# tarjeta-v8.net
KiCad netlist of a schematic drawn in EAGLE
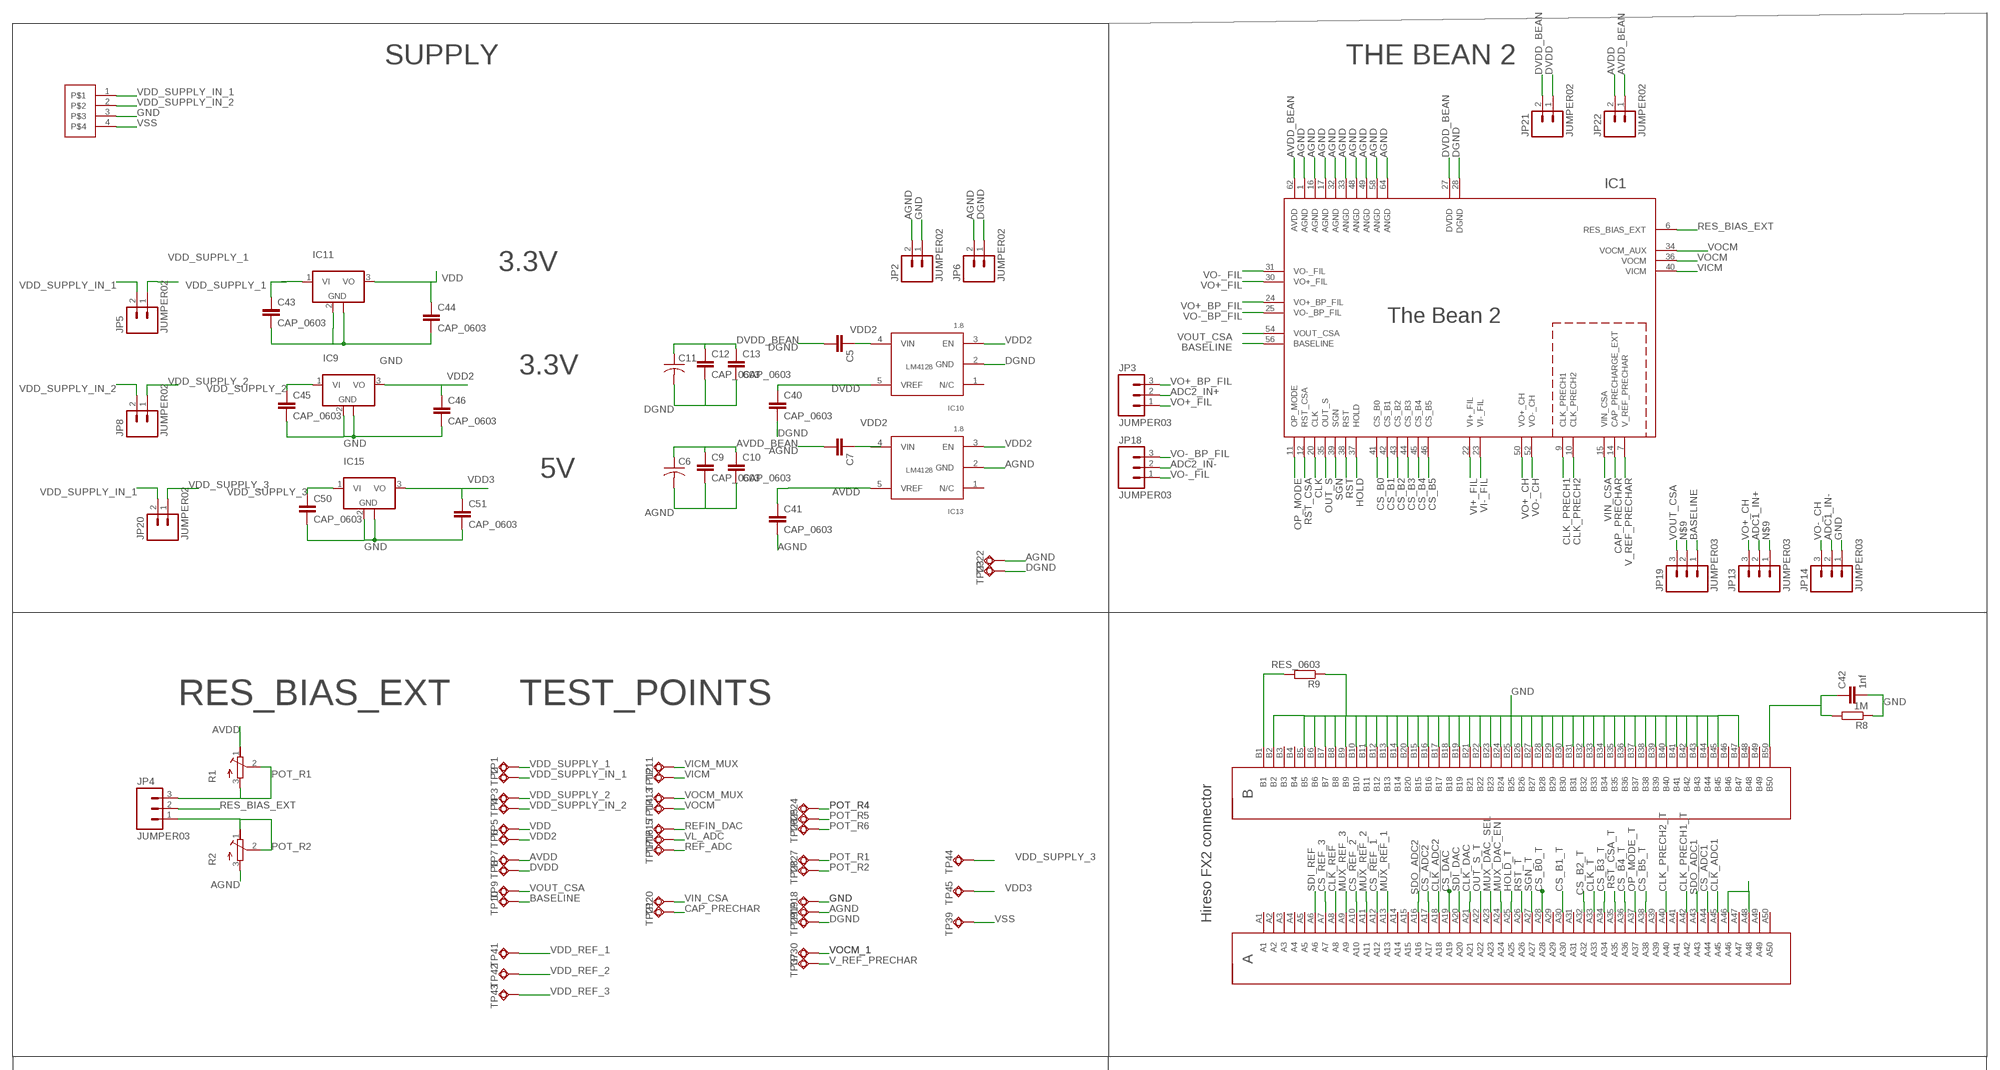
[diagram p0: schematic, sheet 1, part 1 of 3]
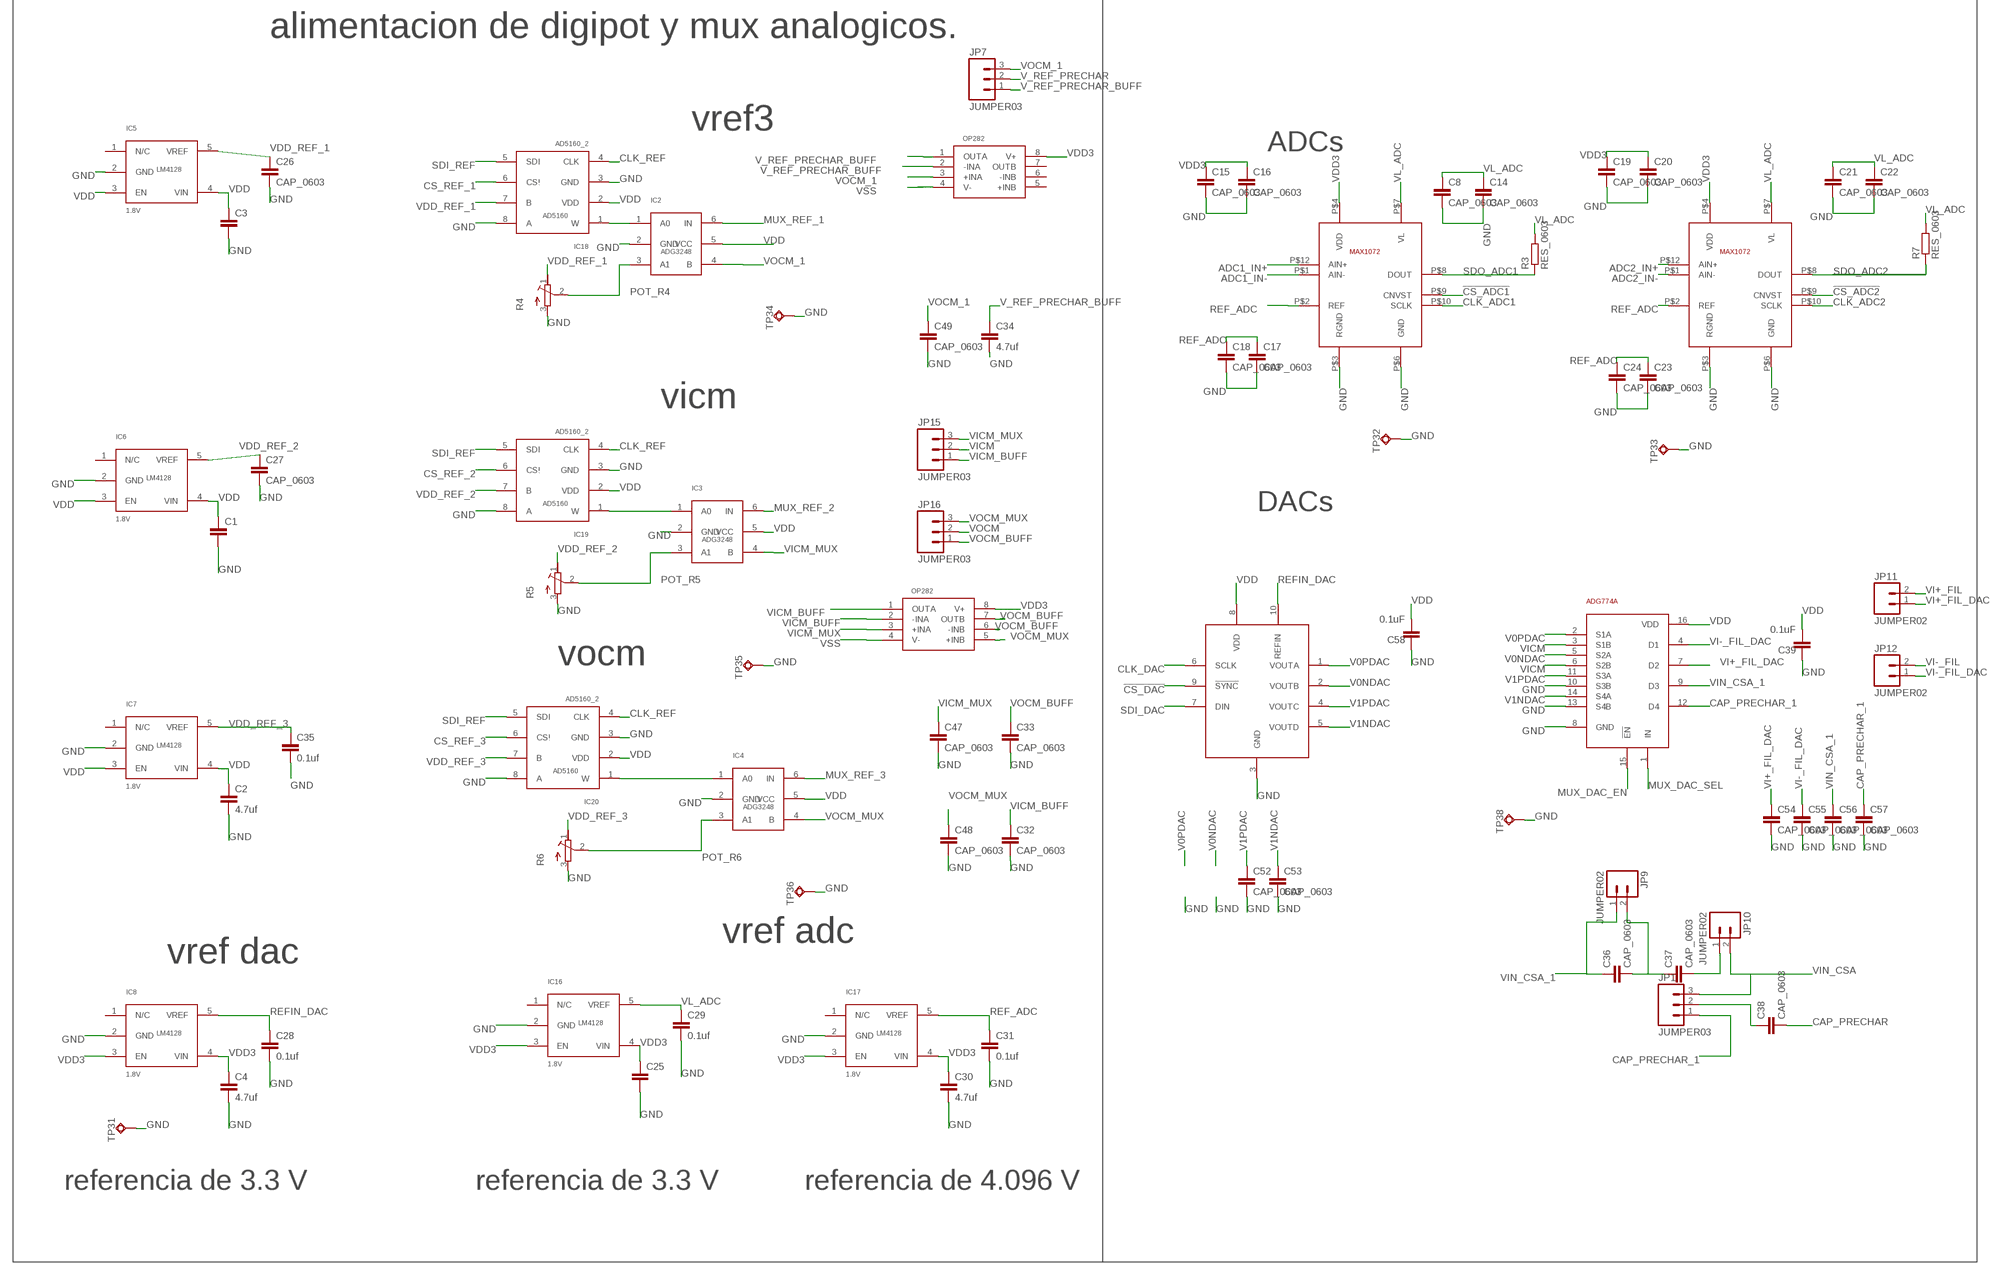
[diagram p1: schematic, sheet 1, part 2 of 3]
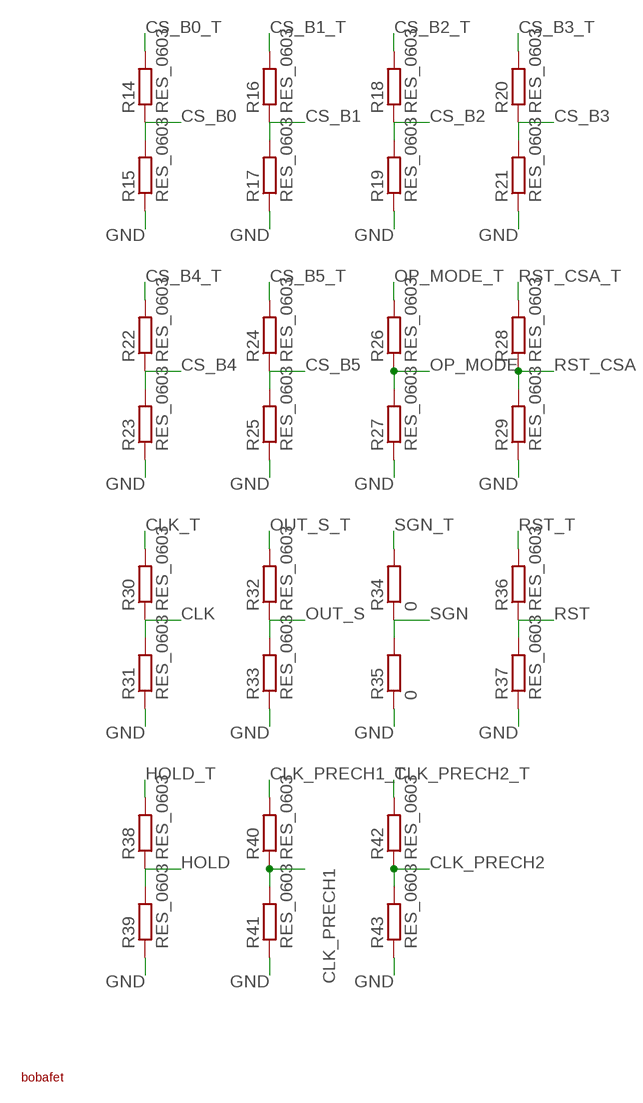
[diagram p2: schematic, sheet 1, part 3 of 3]

(export (version "E")
  (design (tool "Eeschema 10.0.6"))
  (components
    (comp (ref "C1")
      (value "CAP_0402")
      (footprint "eagle-import:C0402")
      (libsource (lib "eagle-import") (part "CAP_0402"))
    )
    (comp (ref "C2")
      (value "4.7uf")
      (footprint "eagle-import:C0402")
      (libsource (lib "eagle-import") (part "CAP_0402"))
    )
    (comp (ref "C3")
      (value "CAP_0402")
      (footprint "eagle-import:C0402")
      (libsource (lib "eagle-import") (part "CAP_0402"))
    )
    (comp (ref "C4")
      (value "4.7uf")
      (footprint "eagle-import:C0402")
      (libsource (lib "eagle-import") (part "CAP_0402"))
    )
    (comp (ref "C5")
      (value "CAP_0402")
      (footprint "eagle-import:C0402")
      (libsource (lib "eagle-import") (part "CAP_0402"))
    )
    (comp (ref "C6")
      (value "CAP_0805")
      (footprint "eagle-import:C0805")
      (libsource (lib "eagle-import") (part "CAP_0805"))
    )
    (comp (ref "C7")
      (value "CAP_0402")
      (footprint "eagle-import:C0402")
      (libsource (lib "eagle-import") (part "CAP_0402"))
    )
    (comp (ref "C8")
      (value "CAP_0603")
      (footprint "eagle-import:C0603")
      (libsource (lib "eagle-import") (part "CAP_0603"))
    )
    (comp (ref "C9")
      (value "CAP_0603")
      (footprint "eagle-import:C0603")
      (libsource (lib "eagle-import") (part "CAP_0603"))
    )
    (comp (ref "C10")
      (value "CAP_0603")
      (footprint "eagle-import:C0603")
      (libsource (lib "eagle-import") (part "CAP_0603"))
    )
    (comp (ref "C11")
      (value "CAP_0805")
      (footprint "eagle-import:C0805")
      (libsource (lib "eagle-import") (part "CAP_0805"))
    )
    (comp (ref "C12")
      (value "CAP_0603")
      (footprint "eagle-import:C0603")
      (libsource (lib "eagle-import") (part "CAP_0603"))
    )
    (comp (ref "C13")
      (value "CAP_0603")
      (footprint "eagle-import:C0603")
      (libsource (lib "eagle-import") (part "CAP_0603"))
    )
    (comp (ref "C14")
      (value "CAP_0603")
      (footprint "eagle-import:C0603")
      (libsource (lib "eagle-import") (part "CAP_0603"))
    )
    (comp (ref "C15")
      (value "CAP_0603")
      (footprint "eagle-import:C0603")
      (libsource (lib "eagle-import") (part "CAP_0603"))
    )
    (comp (ref "C16")
      (value "CAP_0603")
      (footprint "eagle-import:C0603")
      (libsource (lib "eagle-import") (part "CAP_0603"))
    )
    (comp (ref "C17")
      (value "CAP_0603")
      (footprint "eagle-import:C0603")
      (libsource (lib "eagle-import") (part "CAP_0603"))
    )
    (comp (ref "C18")
      (value "CAP_0603")
      (footprint "eagle-import:C0603")
      (libsource (lib "eagle-import") (part "CAP_0603"))
    )
    (comp (ref "C19")
      (value "CAP_0603")
      (footprint "eagle-import:C0603")
      (libsource (lib "eagle-import") (part "CAP_0603"))
    )
    (comp (ref "C20")
      (value "CAP_0603")
      (footprint "eagle-import:C0603")
      (libsource (lib "eagle-import") (part "CAP_0603"))
    )
    (comp (ref "C21")
      (value "CAP_0603")
      (footprint "eagle-import:C0603")
      (libsource (lib "eagle-import") (part "CAP_0603"))
    )
    (comp (ref "C22")
      (value "CAP_0603")
      (footprint "eagle-import:C0603")
      (libsource (lib "eagle-import") (part "CAP_0603"))
    )
    (comp (ref "C23")
      (value "CAP_0603")
      (footprint "eagle-import:C0603")
      (libsource (lib "eagle-import") (part "CAP_0603"))
    )
    (comp (ref "C24")
      (value "CAP_0603")
      (footprint "eagle-import:C0603")
      (libsource (lib "eagle-import") (part "CAP_0603"))
    )
    (comp (ref "C25")
      (value "CAP_0402")
      (footprint "eagle-import:C0402")
      (libsource (lib "eagle-import") (part "CAP_0402"))
    )
    (comp (ref "C26")
      (value "CAP_0603")
      (footprint "eagle-import:C0603")
      (libsource (lib "eagle-import") (part "CAP_0603"))
    )
    (comp (ref "C27")
      (value "CAP_0603")
      (footprint "eagle-import:C0603")
      (libsource (lib "eagle-import") (part "CAP_0603"))
    )
    (comp (ref "C28")
      (value "0.1uf")
      (footprint "eagle-import:C0603")
      (libsource (lib "eagle-import") (part "CAP_0603"))
    )
    (comp (ref "C29")
      (value "0.1uf")
      (footprint "eagle-import:C0603")
      (libsource (lib "eagle-import") (part "CAP_0603"))
    )
    (comp (ref "C30")
      (value "4.7uf")
      (footprint "eagle-import:C0402")
      (libsource (lib "eagle-import") (part "CAP_0402"))
    )
    (comp (ref "C31")
      (value "0.1uf")
      (footprint "eagle-import:C0603")
      (libsource (lib "eagle-import") (part "CAP_0603"))
    )
    (comp (ref "C32")
      (value "CAP_0603")
      (footprint "eagle-import:C0603")
      (libsource (lib "eagle-import") (part "CAP_0603"))
    )
    (comp (ref "C33")
      (value "CAP_0603")
      (footprint "eagle-import:C0603")
      (libsource (lib "eagle-import") (part "CAP_0603"))
    )
    (comp (ref "C34")
      (value "4.7uf")
      (footprint "eagle-import:C0603")
      (libsource (lib "eagle-import") (part "CAP_0603"))
    )
    (comp (ref "C35")
      (value "0.1uf")
      (footprint "eagle-import:C0603")
      (libsource (lib "eagle-import") (part "CAP_0603"))
    )
    (comp (ref "C36")
      (value "CAP_0603")
      (footprint "eagle-import:C0603")
      (libsource (lib "eagle-import") (part "CAP_0603"))
    )
    (comp (ref "C37")
      (value "CAP_0603")
      (footprint "eagle-import:C0603")
      (libsource (lib "eagle-import") (part "CAP_0603"))
    )
    (comp (ref "C38")
      (value "CAP_0603")
      (footprint "eagle-import:C0603")
      (libsource (lib "eagle-import") (part "CAP_0603"))
    )
    (comp (ref "C39")
      (value "0.1uF")
      (footprint "eagle-import:C0603")
      (libsource (lib "eagle-import") (part "CAP_0603"))
    )
    (comp (ref "C40")
      (value "CAP_0603")
      (footprint "eagle-import:C0603")
      (libsource (lib "eagle-import") (part "CAP_0603"))
    )
    (comp (ref "C41")
      (value "CAP_0603")
      (footprint "eagle-import:C0603")
      (libsource (lib "eagle-import") (part "CAP_0603"))
    )
    (comp (ref "C42")
      (value "1nf")
      (footprint "eagle-import:C0603")
      (libsource (lib "eagle-import") (part "CAP_0603"))
    )
    (comp (ref "C43")
      (value "CAP_0603")
      (footprint "eagle-import:C0603")
      (libsource (lib "eagle-import") (part "CAP_0603"))
    )
    (comp (ref "C44")
      (value "CAP_0603")
      (footprint "eagle-import:C0603")
      (libsource (lib "eagle-import") (part "CAP_0603"))
    )
    (comp (ref "C45")
      (value "CAP_0603")
      (footprint "eagle-import:C0603")
      (libsource (lib "eagle-import") (part "CAP_0603"))
    )
    (comp (ref "C46")
      (value "CAP_0603")
      (footprint "eagle-import:C0603")
      (libsource (lib "eagle-import") (part "CAP_0603"))
    )
    (comp (ref "C47")
      (value "CAP_0603")
      (footprint "eagle-import:C0603")
      (libsource (lib "eagle-import") (part "CAP_0603"))
    )
    (comp (ref "C48")
      (value "CAP_0603")
      (footprint "eagle-import:C0603")
      (libsource (lib "eagle-import") (part "CAP_0603"))
    )
    (comp (ref "C49")
      (value "CAP_0603")
      (footprint "eagle-import:C0603")
      (libsource (lib "eagle-import") (part "CAP_0603"))
    )
    (comp (ref "C50")
      (value "CAP_0603")
      (footprint "eagle-import:C0603")
      (libsource (lib "eagle-import") (part "CAP_0603"))
    )
    (comp (ref "C51")
      (value "CAP_0603")
      (footprint "eagle-import:C0603")
      (libsource (lib "eagle-import") (part "CAP_0603"))
    )
    (comp (ref "C52")
      (value "CAP_0603")
      (footprint "eagle-import:C0603")
      (libsource (lib "eagle-import") (part "CAP_0603"))
    )
    (comp (ref "C53")
      (value "CAP_0603")
      (footprint "eagle-import:C0603")
      (libsource (lib "eagle-import") (part "CAP_0603"))
    )
    (comp (ref "C54")
      (value "CAP_0603")
      (footprint "eagle-import:C0603")
      (libsource (lib "eagle-import") (part "CAP_0603"))
    )
    (comp (ref "C55")
      (value "CAP_0603")
      (footprint "eagle-import:C0603")
      (libsource (lib "eagle-import") (part "CAP_0603"))
    )
    (comp (ref "C56")
      (value "CAP_0603")
      (footprint "eagle-import:C0603")
      (libsource (lib "eagle-import") (part "CAP_0603"))
    )
    (comp (ref "C57")
      (value "CAP_0603")
      (footprint "eagle-import:C0603")
      (libsource (lib "eagle-import") (part "CAP_0603"))
    )
    (comp (ref "C58")
      (value "0.1uF")
      (footprint "eagle-import:C0603")
      (libsource (lib "eagle-import") (part "CAP_0603"))
    )
    (comp (ref "IC1")
      (value "THE_BEAN_2")
      (footprint "eagle-import:QFN64")
      (libsource (lib "eagle-import") (part "THE_BEAN_2"))
    )
    (comp (ref "IC2")
      (value "ADG3248")
      (footprint "eagle-import:SC70")
      (libsource (lib "eagle-import") (part "ADG3248"))
    )
    (comp (ref "IC3")
      (value "ADG3248")
      (footprint "eagle-import:SC70")
      (libsource (lib "eagle-import") (part "ADG3248"))
    )
    (comp (ref "IC4")
      (value "ADG3248")
      (footprint "eagle-import:SC70")
      (libsource (lib "eagle-import") (part "ADG3248"))
    )
    (comp (ref "IC5")
      (value "1.8V")
      (footprint "eagle-import:SOT23-5L_2")
      (libsource (lib "eagle-import") (part "LM4128_2"))
    )
    (comp (ref "IC6")
      (value "1.8V")
      (footprint "eagle-import:SOT23-5L_2")
      (libsource (lib "eagle-import") (part "LM4128_2"))
    )
    (comp (ref "IC7")
      (value "1.8V")
      (footprint "eagle-import:SOT23-5L_2")
      (libsource (lib "eagle-import") (part "LM4128_2"))
    )
    (comp (ref "IC8")
      (value "1.8V")
      (footprint "eagle-import:SOT23-5L_2")
      (libsource (lib "eagle-import") (part "LM4128_2"))
    )
    (comp (ref "IC9")
      (value "UA78M")
      (footprint "eagle-import:SOT223")
      (libsource (lib "eagle-import") (part "UA78M"))
    )
    (comp (ref "IC10")
      (value "1.8")
      (footprint "eagle-import:SOT23-5L_2")
      (libsource (lib "eagle-import") (part "LM4128_2"))
    )
    (comp (ref "IC11")
      (value "UA78M")
      (footprint "eagle-import:SOT223")
      (libsource (lib "eagle-import") (part "UA78M"))
    )
    (comp (ref "IC12")
      (value "OP282")
      (footprint "eagle-import:SOIC8")
      (libsource (lib "eagle-import") (part "OP282"))
    )
    (comp (ref "IC13")
      (value "1.8")
      (footprint "eagle-import:SOT23-5L_2")
      (libsource (lib "eagle-import") (part "LM4128_2"))
    )
    (comp (ref "IC14")
      (value "OP282")
      (footprint "eagle-import:SOIC8")
      (libsource (lib "eagle-import") (part "OP282"))
    )
    (comp (ref "IC15")
      (value "UA78M")
      (footprint "eagle-import:SOT223")
      (libsource (lib "eagle-import") (part "UA78M"))
    )
    (comp (ref "IC16")
      (value "1.8V")
      (footprint "eagle-import:SOT23-5L_2")
      (libsource (lib "eagle-import") (part "LM4128_2"))
    )
    (comp (ref "IC17")
      (value "1.8V")
      (footprint "eagle-import:SOT23-5L_2")
      (libsource (lib "eagle-import") (part "LM4128_2"))
    )
    (comp (ref "IC18")
      (value "AD5160_2")
      (footprint "eagle-import:SOT23-8_2")
      (libsource (lib "eagle-import") (part "AD5160_2"))
    )
    (comp (ref "IC19")
      (value "AD5160_2")
      (footprint "eagle-import:SOT23-8_2")
      (libsource (lib "eagle-import") (part "AD5160_2"))
    )
    (comp (ref "IC20")
      (value "AD5160_2")
      (footprint "eagle-import:SOT23-8_2")
      (libsource (lib "eagle-import") (part "AD5160_2"))
    )
    (comp (ref "IC21")
      (value "ADG774A")
      (footprint "eagle-import:QSOP16")
      (libsource (lib "eagle-import") (part "ADG774A"))
    )
    (comp (ref "IC22")
      (value "MAX1072")
      (footprint "eagle-import:TQFN12")
      (libsource (lib "eagle-import") (part "MAX1072"))
    )
    (comp (ref "IC23")
      (value "DAC7554")
      (footprint "eagle-import:MSOP10")
      (libsource (lib "eagle-import") (part "DAC7554"))
    )
    (comp (ref "IC24")
      (value "MAX1072")
      (footprint "eagle-import:TQFN12")
      (libsource (lib "eagle-import") (part "MAX1072"))
    )
    (comp (ref "J1")
      (value "HIRESO_FX_CONNECTOR")
      (footprint "eagle-import:FX2-100S-1.27")
      (libsource (lib "eagle-import") (part "HIRESO_FX_CONNECTOR"))
    )
    (comp (ref "JP1")
      (value "JUMPER03")
      (footprint "eagle-import:1X03")
      (libsource (lib "eagle-import") (part "JUMPER03"))
    )
    (comp (ref "JP2")
      (value "JUMPER02")
      (footprint "eagle-import:1X02")
      (libsource (lib "eagle-import") (part "JUMPER02"))
    )
    (comp (ref "JP3")
      (value "JUMPER03")
      (footprint "eagle-import:1X03")
      (libsource (lib "eagle-import") (part "JUMPER03"))
    )
    (comp (ref "JP4")
      (value "JUMPER03")
      (footprint "eagle-import:1X03")
      (libsource (lib "eagle-import") (part "JUMPER03"))
    )
    (comp (ref "JP5")
      (value "JUMPER02")
      (footprint "eagle-import:1X02")
      (libsource (lib "eagle-import") (part "JUMPER02"))
    )
    (comp (ref "JP6")
      (value "JUMPER02")
      (footprint "eagle-import:1X02")
      (libsource (lib "eagle-import") (part "JUMPER02"))
    )
    (comp (ref "JP7")
      (value "JUMPER03")
      (footprint "eagle-import:1X03")
      (libsource (lib "eagle-import") (part "JUMPER03"))
    )
    (comp (ref "JP8")
      (value "JUMPER02")
      (footprint "eagle-import:1X02")
      (libsource (lib "eagle-import") (part "JUMPER02"))
    )
    (comp (ref "JP9")
      (value "JUMPER02")
      (footprint "eagle-import:1X02")
      (libsource (lib "eagle-import") (part "JUMPER02"))
    )
    (comp (ref "JP10")
      (value "JUMPER02")
      (footprint "eagle-import:1X02")
      (libsource (lib "eagle-import") (part "JUMPER02"))
    )
    (comp (ref "JP11")
      (value "JUMPER02")
      (footprint "eagle-import:1X02")
      (libsource (lib "eagle-import") (part "JUMPER02"))
    )
    (comp (ref "JP12")
      (value "JUMPER02")
      (footprint "eagle-import:1X02")
      (libsource (lib "eagle-import") (part "JUMPER02"))
    )
    (comp (ref "JP13")
      (value "JUMPER03")
      (footprint "eagle-import:1X03")
      (libsource (lib "eagle-import") (part "JUMPER03"))
    )
    (comp (ref "JP14")
      (value "JUMPER03")
      (footprint "eagle-import:1X03")
      (libsource (lib "eagle-import") (part "JUMPER03"))
    )
    (comp (ref "JP15")
      (value "JUMPER03")
      (footprint "eagle-import:1X03")
      (libsource (lib "eagle-import") (part "JUMPER03"))
    )
    (comp (ref "JP16")
      (value "JUMPER03")
      (footprint "eagle-import:1X03")
      (libsource (lib "eagle-import") (part "JUMPER03"))
    )
    (comp (ref "JP17")
      (value "JUMPER04")
      (footprint "eagle-import:1X04")
      (libsource (lib "eagle-import") (part "JUMPER04"))
    )
    (comp (ref "JP18")
      (value "JUMPER03")
      (footprint "eagle-import:1X03")
      (libsource (lib "eagle-import") (part "JUMPER03"))
    )
    (comp (ref "JP19")
      (value "JUMPER03")
      (footprint "eagle-import:1X03")
      (libsource (lib "eagle-import") (part "JUMPER03"))
    )
    (comp (ref "JP20")
      (value "JUMPER02")
      (footprint "eagle-import:1X02")
      (libsource (lib "eagle-import") (part "JUMPER02"))
    )
    (comp (ref "JP21")
      (value "JUMPER02")
      (footprint "eagle-import:1X02")
      (libsource (lib "eagle-import") (part "JUMPER02"))
    )
    (comp (ref "JP22")
      (value "JUMPER02")
      (footprint "eagle-import:1X02")
      (libsource (lib "eagle-import") (part "JUMPER02"))
    )
    (comp (ref "R1")
      (value "TRIMMER_ST5")
      (footprint "eagle-import:ST-5EW")
      (libsource (lib "eagle-import") (part "TRIMMER_ST5"))
    )
    (comp (ref "R2")
      (value "TRIMMER_ST5")
      (footprint "eagle-import:ST-5EW")
      (libsource (lib "eagle-import") (part "TRIMMER_ST5"))
    )
    (comp (ref "R3")
      (value "RES_0603")
      (footprint "eagle-import:R0603")
      (libsource (lib "eagle-import") (part "RES_0603"))
    )
    (comp (ref "R4")
      (value "TRIMMER_ST5")
      (footprint "eagle-import:ST-5EW")
      (libsource (lib "eagle-import") (part "TRIMMER_ST5"))
    )
    (comp (ref "R5")
      (value "TRIMMER_ST5")
      (footprint "eagle-import:ST-5EW")
      (libsource (lib "eagle-import") (part "TRIMMER_ST5"))
    )
    (comp (ref "R6")
      (value "TRIMMER_ST5")
      (footprint "eagle-import:ST-5EW")
      (libsource (lib "eagle-import") (part "TRIMMER_ST5"))
    )
    (comp (ref "R7")
      (value "RES_0603")
      (footprint "eagle-import:R0603")
      (libsource (lib "eagle-import") (part "RES_0603"))
    )
    (comp (ref "R8")
      (value "1M")
      (footprint "eagle-import:R0603")
      (libsource (lib "eagle-import") (part "RES_0603"))
    )
    (comp (ref "R9")
      (value "RES_0603")
      (footprint "eagle-import:R0603")
      (libsource (lib "eagle-import") (part "RES_0603"))
    )
    (comp (ref "R14")
      (value "RES_0603")
      (footprint "eagle-import:R0603")
      (libsource (lib "eagle-import") (part "RES_0603"))
    )
    (comp (ref "R15")
      (value "RES_0603")
      (footprint "eagle-import:R0603")
      (libsource (lib "eagle-import") (part "RES_0603"))
    )
    (comp (ref "R16")
      (value "RES_0603")
      (footprint "eagle-import:R0603")
      (libsource (lib "eagle-import") (part "RES_0603"))
    )
    (comp (ref "R17")
      (value "RES_0603")
      (footprint "eagle-import:R0603")
      (libsource (lib "eagle-import") (part "RES_0603"))
    )
    (comp (ref "R18")
      (value "RES_0603")
      (footprint "eagle-import:R0603")
      (libsource (lib "eagle-import") (part "RES_0603"))
    )
    (comp (ref "R19")
      (value "RES_0603")
      (footprint "eagle-import:R0603")
      (libsource (lib "eagle-import") (part "RES_0603"))
    )
    (comp (ref "R20")
      (value "RES_0603")
      (footprint "eagle-import:R0603")
      (libsource (lib "eagle-import") (part "RES_0603"))
    )
    (comp (ref "R21")
      (value "RES_0603")
      (footprint "eagle-import:R0603")
      (libsource (lib "eagle-import") (part "RES_0603"))
    )
    (comp (ref "R22")
      (value "RES_0603")
      (footprint "eagle-import:R0603")
      (libsource (lib "eagle-import") (part "RES_0603"))
    )
    (comp (ref "R23")
      (value "RES_0603")
      (footprint "eagle-import:R0603")
      (libsource (lib "eagle-import") (part "RES_0603"))
    )
    (comp (ref "R24")
      (value "RES_0603")
      (footprint "eagle-import:R0603")
      (libsource (lib "eagle-import") (part "RES_0603"))
    )
    (comp (ref "R25")
      (value "RES_0603")
      (footprint "eagle-import:R0603")
      (libsource (lib "eagle-import") (part "RES_0603"))
    )
    (comp (ref "R26")
      (value "RES_0603")
      (footprint "eagle-import:R0603")
      (libsource (lib "eagle-import") (part "RES_0603"))
    )
    (comp (ref "R27")
      (value "RES_0603")
      (footprint "eagle-import:R0603")
      (libsource (lib "eagle-import") (part "RES_0603"))
    )
    (comp (ref "R28")
      (value "RES_0603")
      (footprint "eagle-import:R0603")
      (libsource (lib "eagle-import") (part "RES_0603"))
    )
    (comp (ref "R29")
      (value "RES_0603")
      (footprint "eagle-import:R0603")
      (libsource (lib "eagle-import") (part "RES_0603"))
    )
    (comp (ref "R30")
      (value "RES_0603")
      (footprint "eagle-import:R0603")
      (libsource (lib "eagle-import") (part "RES_0603"))
    )
    (comp (ref "R31")
      (value "RES_0603")
      (footprint "eagle-import:R0603")
      (libsource (lib "eagle-import") (part "RES_0603"))
    )
    (comp (ref "R32")
      (value "RES_0603")
      (footprint "eagle-import:R0603")
      (libsource (lib "eagle-import") (part "RES_0603"))
    )
    (comp (ref "R33")
      (value "RES_0603")
      (footprint "eagle-import:R0603")
      (libsource (lib "eagle-import") (part "RES_0603"))
    )
    (comp (ref "R34")
      (value "0")
      (footprint "eagle-import:R0603")
      (libsource (lib "eagle-import") (part "RES_0603"))
    )
    (comp (ref "R35")
      (value "0")
      (footprint "eagle-import:R0603")
      (libsource (lib "eagle-import") (part "RES_0603"))
    )
    (comp (ref "R36")
      (value "RES_0603")
      (footprint "eagle-import:R0603")
      (libsource (lib "eagle-import") (part "RES_0603"))
    )
    (comp (ref "R37")
      (value "RES_0603")
      (footprint "eagle-import:R0603")
      (libsource (lib "eagle-import") (part "RES_0603"))
    )
    (comp (ref "R38")
      (value "RES_0603")
      (footprint "eagle-import:R0603")
      (libsource (lib "eagle-import") (part "RES_0603"))
    )
    (comp (ref "R39")
      (value "RES_0603")
      (footprint "eagle-import:R0603")
      (libsource (lib "eagle-import") (part "RES_0603"))
    )
    (comp (ref "R40")
      (value "RES_0603")
      (footprint "eagle-import:R0603")
      (libsource (lib "eagle-import") (part "RES_0603"))
    )
    (comp (ref "R41")
      (value "RES_0603")
      (footprint "eagle-import:R0603")
      (libsource (lib "eagle-import") (part "RES_0603"))
    )
    (comp (ref "R42")
      (value "RES_0603")
      (footprint "eagle-import:R0603")
      (libsource (lib "eagle-import") (part "RES_0603"))
    )
    (comp (ref "R43")
      (value "RES_0603")
      (footprint "eagle-import:R0603")
      (libsource (lib "eagle-import") (part "RES_0603"))
    )
    (comp (ref "TP1")
      (value "TEST_POINT")
      (footprint "eagle-import:TP")
      (libsource (lib "eagle-import") (part "TEST_POINT"))
    )
    (comp (ref "TP2")
      (value "TEST_POINT")
      (footprint "eagle-import:TP")
      (libsource (lib "eagle-import") (part "TEST_POINT"))
    )
    (comp (ref "TP3")
      (value "TEST_POINT")
      (footprint "eagle-import:TP")
      (libsource (lib "eagle-import") (part "TEST_POINT"))
    )
    (comp (ref "TP4")
      (value "TEST_POINT")
      (footprint "eagle-import:TP")
      (libsource (lib "eagle-import") (part "TEST_POINT"))
    )
    (comp (ref "TP5")
      (value "TEST_POINT")
      (footprint "eagle-import:TP")
      (libsource (lib "eagle-import") (part "TEST_POINT"))
    )
    (comp (ref "TP6")
      (value "TEST_POINT")
      (footprint "eagle-import:TP")
      (libsource (lib "eagle-import") (part "TEST_POINT"))
    )
    (comp (ref "TP7")
      (value "TEST_POINT")
      (footprint "eagle-import:TP")
      (libsource (lib "eagle-import") (part "TEST_POINT"))
    )
    (comp (ref "TP8")
      (value "TEST_POINT")
      (footprint "eagle-import:TP")
      (libsource (lib "eagle-import") (part "TEST_POINT"))
    )
    (comp (ref "TP9")
      (value "TEST_POINT")
      (footprint "eagle-import:TP")
      (libsource (lib "eagle-import") (part "TEST_POINT"))
    )
    (comp (ref "TP10")
      (value "TEST_POINT")
      (footprint "eagle-import:TP")
      (libsource (lib "eagle-import") (part "TEST_POINT"))
    )
    (comp (ref "TP11")
      (value "TEST_POINT")
      (footprint "eagle-import:TP")
      (libsource (lib "eagle-import") (part "TEST_POINT"))
    )
    (comp (ref "TP12")
      (value "TEST_POINT")
      (footprint "eagle-import:TP")
      (libsource (lib "eagle-import") (part "TEST_POINT"))
    )
    (comp (ref "TP13")
      (value "TEST_POINT")
      (footprint "eagle-import:TP")
      (libsource (lib "eagle-import") (part "TEST_POINT"))
    )
    (comp (ref "TP14")
      (value "TEST_POINT")
      (footprint "eagle-import:TP")
      (libsource (lib "eagle-import") (part "TEST_POINT"))
    )
    (comp (ref "TP15")
      (value "TEST_POINT")
      (footprint "eagle-import:TP")
      (libsource (lib "eagle-import") (part "TEST_POINT"))
    )
    (comp (ref "TP16")
      (value "TEST_POINT")
      (footprint "eagle-import:TP")
      (libsource (lib "eagle-import") (part "TEST_POINT"))
    )
    (comp (ref "TP17")
      (value "TEST_POINT")
      (footprint "eagle-import:TP")
      (libsource (lib "eagle-import") (part "TEST_POINT"))
    )
    (comp (ref "TP18")
      (value "TEST_POINT")
      (footprint "eagle-import:TP")
      (libsource (lib "eagle-import") (part "TEST_POINT"))
    )
    (comp (ref "TP19")
      (value "TEST_POINT")
      (footprint "eagle-import:TP")
      (libsource (lib "eagle-import") (part "TEST_POINT"))
    )
    (comp (ref "TP20")
      (value "TEST_POINT")
      (footprint "eagle-import:TP")
      (libsource (lib "eagle-import") (part "TEST_POINT"))
    )
    (comp (ref "TP21")
      (value "TEST_POINT")
      (footprint "eagle-import:TP")
      (libsource (lib "eagle-import") (part "TEST_POINT"))
    )
    (comp (ref "TP22")
      (value "TEST_POINT")
      (footprint "eagle-import:TP")
      (libsource (lib "eagle-import") (part "TEST_POINT"))
    )
    (comp (ref "TP23")
      (value "TEST_POINT")
      (footprint "eagle-import:TP")
      (libsource (lib "eagle-import") (part "TEST_POINT"))
    )
    (comp (ref "TP24")
      (value "TEST_POINT")
      (footprint "eagle-import:TP")
      (libsource (lib "eagle-import") (part "TEST_POINT"))
    )
    (comp (ref "TP25")
      (value "TEST_POINT")
      (footprint "eagle-import:TP")
      (libsource (lib "eagle-import") (part "TEST_POINT"))
    )
    (comp (ref "TP26")
      (value "TEST_POINT")
      (footprint "eagle-import:TP")
      (libsource (lib "eagle-import") (part "TEST_POINT"))
    )
    (comp (ref "TP27")
      (value "TEST_POINT")
      (footprint "eagle-import:TP")
      (libsource (lib "eagle-import") (part "TEST_POINT"))
    )
    (comp (ref "TP28")
      (value "TEST_POINT")
      (footprint "eagle-import:TP")
      (libsource (lib "eagle-import") (part "TEST_POINT"))
    )
    (comp (ref "TP29")
      (value "TEST_POINT")
      (footprint "eagle-import:TP")
      (libsource (lib "eagle-import") (part "TEST_POINT"))
    )
    (comp (ref "TP30")
      (value "TEST_POINT")
      (footprint "eagle-import:TP")
      (libsource (lib "eagle-import") (part "TEST_POINT"))
    )
    (comp (ref "TP31")
      (value "TEST_POINT")
      (footprint "eagle-import:TP")
      (libsource (lib "eagle-import") (part "TEST_POINT"))
    )
    (comp (ref "TP32")
      (value "TEST_POINT")
      (footprint "eagle-import:TP")
      (libsource (lib "eagle-import") (part "TEST_POINT"))
    )
    (comp (ref "TP33")
      (value "TEST_POINT")
      (footprint "eagle-import:TP")
      (libsource (lib "eagle-import") (part "TEST_POINT"))
    )
    (comp (ref "TP34")
      (value "TEST_POINT")
      (footprint "eagle-import:TP")
      (libsource (lib "eagle-import") (part "TEST_POINT"))
    )
    (comp (ref "TP35")
      (value "TEST_POINT")
      (footprint "eagle-import:TP")
      (libsource (lib "eagle-import") (part "TEST_POINT"))
    )
    (comp (ref "TP36")
      (value "TEST_POINT")
      (footprint "eagle-import:TP")
      (libsource (lib "eagle-import") (part "TEST_POINT"))
    )
    (comp (ref "TP37")
      (value "TEST_POINT")
      (footprint "eagle-import:TP")
      (libsource (lib "eagle-import") (part "TEST_POINT"))
    )
    (comp (ref "TP38")
      (value "TEST_POINT")
      (footprint "eagle-import:TP")
      (libsource (lib "eagle-import") (part "TEST_POINT"))
    )
    (comp (ref "TP39")
      (value "TEST_POINT")
      (footprint "eagle-import:TP")
      (libsource (lib "eagle-import") (part "TEST_POINT"))
    )
    (comp (ref "TP41")
      (value "TEST_POINT")
      (footprint "eagle-import:TP")
      (libsource (lib "eagle-import") (part "TEST_POINT"))
    )
    (comp (ref "TP42")
      (value "TEST_POINT")
      (footprint "eagle-import:TP")
      (libsource (lib "eagle-import") (part "TEST_POINT"))
    )
    (comp (ref "TP43")
      (value "TEST_POINT")
      (footprint "eagle-import:TP")
      (libsource (lib "eagle-import") (part "TEST_POINT"))
    )
    (comp (ref "TP44")
      (value "TEST_POINT")
      (footprint "eagle-import:TP")
      (libsource (lib "eagle-import") (part "TEST_POINT"))
    )
    (comp (ref "TP45")
      (value "TEST_POINT")
      (footprint "eagle-import:TP")
      (libsource (lib "eagle-import") (part "TEST_POINT"))
    )
    (comp (ref "U$1")
      (value "LOGO")
      (footprint "eagle-import:LOGO")
      (libsource (lib "eagle-import") (part "LOGO"))
    )
  )
  (nets
    (net (code "1") (name "/ADC1_IN+") (class "Default")
      (node (ref "IC22") (pin "P$12") (pinfunction "AIN+_P$12") (pintype "bidirectional"))
      (node (ref "JP13") (pin "2") (pinfunction "2_2") (pintype "passive"))
    )
    (net (code "2") (name "/ADC1_IN-") (class "Default")
      (node (ref "IC22") (pin "P$1") (pinfunction "AIN-_P$1") (pintype "bidirectional"))
      (node (ref "JP14") (pin "2") (pinfunction "2_2") (pintype "passive"))
    )
    (net (code "3") (name "/ADC2_IN+") (class "Default")
      (node (ref "IC24") (pin "P$12") (pinfunction "AIN+_P$12") (pintype "bidirectional"))
      (node (ref "JP3") (pin "2") (pinfunction "2_2") (pintype "passive"))
    )
    (net (code "4") (name "/ADC2_IN-") (class "Default")
      (node (ref "IC24") (pin "P$1") (pinfunction "AIN-_P$1") (pintype "bidirectional"))
      (node (ref "JP18") (pin "2") (pinfunction "2_2") (pintype "passive"))
    )
    (net (code "5") (name "/AGND") (class "Default")
      (node (ref "C10") (pin "2") (pinfunction "2_2") (pintype "passive"))
      (node (ref "C41") (pin "2") (pinfunction "2_2") (pintype "passive"))
      (node (ref "C6") (pin "2") (pinfunction "2_2") (pintype "passive"))
      (node (ref "C7") (pin "2") (pinfunction "2_2") (pintype "passive"))
      (node (ref "C9") (pin "2") (pinfunction "2_2") (pintype "passive"))
      (node (ref "IC1") (pin "1") (pinfunction "AGND_1") (pintype "power_in"))
      (node (ref "IC1") (pin "16") (pinfunction "AGND_16") (pintype "power_in"))
      (node (ref "IC1") (pin "17") (pinfunction "AGND_17") (pintype "power_in"))
      (node (ref "IC1") (pin "32") (pinfunction "AGND_32") (pintype "power_in"))
      (node (ref "IC1") (pin "33") (pinfunction "ANGD_33") (pintype "power_in"))
      (node (ref "IC1") (pin "48") (pinfunction "ANGD_48") (pintype "power_in"))
      (node (ref "IC1") (pin "49") (pinfunction "ANGD_49") (pintype "power_in"))
      (node (ref "IC1") (pin "58") (pinfunction "ANGD_58") (pintype "power_in"))
      (node (ref "IC1") (pin "64") (pinfunction "ANGD_64") (pintype "power_in"))
      (node (ref "IC13") (pin "2") (pinfunction "GND_2") (pintype "bidirectional"))
      (node (ref "JP2") (pin "2") (pinfunction "2_2") (pintype "passive"))
      (node (ref "JP6") (pin "2") (pinfunction "2_2") (pintype "passive"))
      (node (ref "R2") (pin "3") (pinfunction "3_3") (pintype "passive"))
      (node (ref "TP19") (pin "TP") (pinfunction "TP_TP") (pintype "input"))
      (node (ref "TP22") (pin "TP") (pinfunction "TP_TP") (pintype "input"))
    )
    (net (code "6") (name "/AVDD") (class "Default")
      (node (ref "C41") (pin "1") (pinfunction "1_1") (pintype "passive"))
      (node (ref "IC13") (pin "5") (pinfunction "VREF_5") (pintype "bidirectional"))
      (node (ref "JP22") (pin "2") (pinfunction "2_2") (pintype "passive"))
      (node (ref "R1") (pin "1") (pinfunction "1_1") (pintype "passive"))
      (node (ref "TP7") (pin "TP") (pinfunction "TP_TP") (pintype "input"))
    )
    (net (code "7") (name "/AVDD_BEAN") (class "Default")
      (node (ref "C10") (pin "1") (pinfunction "1_1") (pintype "passive"))
      (node (ref "C6") (pin "1") (pinfunction "1_1") (pintype "passive"))
      (node (ref "C9") (pin "1") (pinfunction "1_1") (pintype "passive"))
      (node (ref "IC1") (pin "62") (pinfunction "AVDD_62") (pintype "power_in"))
      (node (ref "JP22") (pin "1") (pinfunction "1_1") (pintype "passive"))
    )
    (net (code "8") (name "/BASELINE") (class "Default")
      (node (ref "IC1") (pin "56") (pinfunction "BASELINE_56") (pintype "output"))
      (node (ref "JP19") (pin "1") (pinfunction "1_1") (pintype "passive"))
      (node (ref "TP10") (pin "TP") (pinfunction "TP_TP") (pintype "input"))
    )
    (net (code "9") (name "/CAP_PRECHAR") (class "Default")
      (node (ref "C38") (pin "2") (pinfunction "2_2") (pintype "passive"))
      (node (ref "IC1") (pin "14") (pinfunction "CAP_PRECHARGE_EXT_14") (pintype "input"))
      (node (ref "TP21") (pin "TP") (pinfunction "TP_TP") (pintype "input"))
    )
    (net (code "10") (name "/CAP_PRECHAR_1") (class "Default")
      (node (ref "C57") (pin "1") (pinfunction "1_1") (pintype "passive"))
      (node (ref "IC21") (pin "12") (pinfunction "D4_12") (pintype "bidirectional"))
      (node (ref "JP1") (pin "1") (pinfunction "1_1") (pintype "passive"))
    )
    (net (code "11") (name "/CLK") (class "Default")
      (node (ref "IC1") (pin "20") (pinfunction "CLK_20") (pintype "bidirectional"))
      (node (ref "R30") (pin "1") (pinfunction "1_1") (pintype "passive"))
      (node (ref "R31") (pin "2") (pinfunction "2_2") (pintype "passive"))
    )
    (net (code "12") (name "/CLK_ADC1") (class "Default")
      (node (ref "IC22") (pin "P$10") (pinfunction "SCLK_P$10") (pintype "bidirectional"))
      (node (ref "J1") (pin "A45") (pinfunction "A45_A45") (pintype "bidirectional"))
    )
    (net (code "13") (name "/CLK_ADC2") (class "Default")
      (node (ref "IC24") (pin "P$10") (pinfunction "SCLK_P$10") (pintype "bidirectional"))
      (node (ref "J1") (pin "A18") (pinfunction "A18_A18") (pintype "bidirectional"))
    )
    (net (code "14") (name "/CLK_DAC") (class "Default")
      (node (ref "IC23") (pin "6") (pinfunction "SCLK_6") (pintype "bidirectional"))
      (node (ref "J1") (pin "A21") (pinfunction "A21_A21") (pintype "bidirectional"))
    )
    (net (code "15") (name "/CLK_PRECH1") (class "Default")
      (node (ref "IC1") (pin "9") (pinfunction "CLK_PRECH1_9") (pintype "bidirectional"))
      (node (ref "R40") (pin "1") (pinfunction "1_1") (pintype "passive"))
      (node (ref "R41") (pin "2") (pinfunction "2_2") (pintype "passive"))
    )
    (net (code "16") (name "/CLK_PRECH1_T") (class "Default")
      (node (ref "J1") (pin "A42") (pinfunction "A42_A42") (pintype "bidirectional"))
      (node (ref "R40") (pin "2") (pinfunction "2_2") (pintype "passive"))
    )
    (net (code "17") (name "/CLK_PRECH2") (class "Default")
      (node (ref "IC1") (pin "10") (pinfunction "CLK_PRECH2_10") (pintype "bidirectional"))
      (node (ref "R42") (pin "1") (pinfunction "1_1") (pintype "passive"))
      (node (ref "R43") (pin "2") (pinfunction "2_2") (pintype "passive"))
    )
    (net (code "18") (name "/CLK_PRECH2_T") (class "Default")
      (node (ref "J1") (pin "A40") (pinfunction "A40_A40") (pintype "bidirectional"))
      (node (ref "R42") (pin "2") (pinfunction "2_2") (pintype "passive"))
    )
    (net (code "19") (name "/CLK_REF") (class "Default")
      (node (ref "IC18") (pin "4") (pinfunction "CLK_4") (pintype "bidirectional"))
      (node (ref "IC19") (pin "4") (pinfunction "CLK_4") (pintype "bidirectional"))
      (node (ref "IC20") (pin "4") (pinfunction "CLK_4") (pintype "bidirectional"))
      (node (ref "J1") (pin "A8") (pinfunction "A8_A8") (pintype "bidirectional"))
    )
    (net (code "20") (name "/CLK_T") (class "Default")
      (node (ref "J1") (pin "A33") (pinfunction "A33_A33") (pintype "bidirectional"))
      (node (ref "R30") (pin "2") (pinfunction "2_2") (pintype "passive"))
    )
    (net (code "21") (name "/CS_B0") (class "Default")
      (node (ref "IC1") (pin "41") (pinfunction "CS_B0_41") (pintype "bidirectional"))
      (node (ref "R14") (pin "1") (pinfunction "1_1") (pintype "passive"))
      (node (ref "R15") (pin "2") (pinfunction "2_2") (pintype "passive"))
    )
    (net (code "22") (name "/CS_B0_T") (class "Default")
      (node (ref "J1") (pin "A28") (pinfunction "A28_A28") (pintype "bidirectional"))
      (node (ref "R14") (pin "2") (pinfunction "2_2") (pintype "passive"))
    )
    (net (code "23") (name "/CS_B1") (class "Default")
      (node (ref "IC1") (pin "42") (pinfunction "CS_B1_42") (pintype "bidirectional"))
      (node (ref "R16") (pin "1") (pinfunction "1_1") (pintype "passive"))
      (node (ref "R17") (pin "2") (pinfunction "2_2") (pintype "passive"))
    )
    (net (code "24") (name "/CS_B1_T") (class "Default")
      (node (ref "J1") (pin "A30") (pinfunction "A30_A30") (pintype "bidirectional"))
      (node (ref "R16") (pin "2") (pinfunction "2_2") (pintype "passive"))
    )
    (net (code "25") (name "/CS_B2") (class "Default")
      (node (ref "IC1") (pin "43") (pinfunction "CS_B2_43") (pintype "bidirectional"))
      (node (ref "R18") (pin "1") (pinfunction "1_1") (pintype "passive"))
      (node (ref "R19") (pin "2") (pinfunction "2_2") (pintype "passive"))
    )
    (net (code "26") (name "/CS_B2_T") (class "Default")
      (node (ref "J1") (pin "A32") (pinfunction "A32_A32") (pintype "bidirectional"))
      (node (ref "R18") (pin "2") (pinfunction "2_2") (pintype "passive"))
    )
    (net (code "27") (name "/CS_B3") (class "Default")
      (node (ref "IC1") (pin "44") (pinfunction "CS_B3_44") (pintype "bidirectional"))
      (node (ref "R20") (pin "1") (pinfunction "1_1") (pintype "passive"))
      (node (ref "R21") (pin "2") (pinfunction "2_2") (pintype "passive"))
    )
    (net (code "28") (name "/CS_B3_T") (class "Default")
      (node (ref "J1") (pin "A34") (pinfunction "A34_A34") (pintype "bidirectional"))
      (node (ref "R20") (pin "2") (pinfunction "2_2") (pintype "passive"))
    )
    (net (code "29") (name "/CS_B4") (class "Default")
      (node (ref "IC1") (pin "45") (pinfunction "CS_B4_45") (pintype "bidirectional"))
      (node (ref "R22") (pin "1") (pinfunction "1_1") (pintype "passive"))
      (node (ref "R23") (pin "2") (pinfunction "2_2") (pintype "passive"))
    )
    (net (code "30") (name "/CS_B4_T") (class "Default")
      (node (ref "J1") (pin "A36") (pinfunction "A36_A36") (pintype "bidirectional"))
      (node (ref "R22") (pin "2") (pinfunction "2_2") (pintype "passive"))
    )
    (net (code "31") (name "/CS_B5") (class "Default")
      (node (ref "IC1") (pin "46") (pinfunction "CS_B5_46") (pintype "bidirectional"))
      (node (ref "R24") (pin "1") (pinfunction "1_1") (pintype "passive"))
      (node (ref "R25") (pin "2") (pinfunction "2_2") (pintype "passive"))
    )
    (net (code "32") (name "/CS_B5_T") (class "Default")
      (node (ref "J1") (pin "A38") (pinfunction "A38_A38") (pintype "bidirectional"))
      (node (ref "R24") (pin "2") (pinfunction "2_2") (pintype "passive"))
    )
    (net (code "33") (name "/CS_REF_1") (class "Default")
      (node (ref "IC18") (pin "6") (pinfunction "CS~{}_6") (pintype "bidirectional"))
      (node (ref "J1") (pin "A12") (pinfunction "A12_A12") (pintype "bidirectional"))
    )
    (net (code "34") (name "/CS_REF_2") (class "Default")
      (node (ref "IC19") (pin "6") (pinfunction "CS~{}_6") (pintype "bidirectional"))
      (node (ref "J1") (pin "A10") (pinfunction "A10_A10") (pintype "bidirectional"))
    )
    (net (code "35") (name "/CS_REF_3") (class "Default")
      (node (ref "IC20") (pin "6") (pinfunction "CS~{}_6") (pintype "bidirectional"))
      (node (ref "J1") (pin "A7") (pinfunction "A7_A7") (pintype "bidirectional"))
    )
    (net (code "36") (name "/DGND") (class "Default")
      (node (ref "C11") (pin "2") (pinfunction "2_2") (pintype "passive"))
      (node (ref "C12") (pin "2") (pinfunction "2_2") (pintype "passive"))
      (node (ref "C13") (pin "2") (pinfunction "2_2") (pintype "passive"))
      (node (ref "C40") (pin "2") (pinfunction "2_2") (pintype "passive"))
      (node (ref "C5") (pin "2") (pinfunction "2_2") (pintype "passive"))
      (node (ref "IC1") (pin "28") (pinfunction "DGND_28") (pintype "power_in"))
      (node (ref "IC10") (pin "2") (pinfunction "GND_2") (pintype "bidirectional"))
      (node (ref "JP6") (pin "1") (pinfunction "1_1") (pintype "passive"))
      (node (ref "TP23") (pin "TP") (pinfunction "TP_TP") (pintype "input"))
      (node (ref "TP29") (pin "TP") (pinfunction "TP_TP") (pintype "input"))
    )
    (net (code "37") (name "/DVDD") (class "Default")
      (node (ref "C40") (pin "1") (pinfunction "1_1") (pintype "passive"))
      (node (ref "IC10") (pin "5") (pinfunction "VREF_5") (pintype "bidirectional"))
      (node (ref "JP21") (pin "1") (pinfunction "1_1") (pintype "passive"))
      (node (ref "TP8") (pin "TP") (pinfunction "TP_TP") (pintype "input"))
    )
    (net (code "38") (name "/DVDD_BEAN") (class "Default")
      (node (ref "C11") (pin "1") (pinfunction "1_1") (pintype "passive"))
      (node (ref "C12") (pin "1") (pinfunction "1_1") (pintype "passive"))
      (node (ref "C13") (pin "1") (pinfunction "1_1") (pintype "passive"))
      (node (ref "IC1") (pin "27") (pinfunction "DVDD_27") (pintype "power_in"))
      (node (ref "JP21") (pin "2") (pinfunction "2_2") (pintype "passive"))
    )
    (net (code "39") (name "/GND") (class "Default")
      (node (ref "C1") (pin "2") (pinfunction "2_2") (pintype "passive"))
      (node (ref "C14") (pin "2") (pinfunction "2_2") (pintype "passive"))
      (node (ref "C15") (pin "2") (pinfunction "2_2") (pintype "passive"))
      (node (ref "C16") (pin "2") (pinfunction "2_2") (pintype "passive"))
      (node (ref "C17") (pin "2") (pinfunction "2_2") (pintype "passive"))
      (node (ref "C18") (pin "2") (pinfunction "2_2") (pintype "passive"))
      (node (ref "C19") (pin "2") (pinfunction "2_2") (pintype "passive"))
      (node (ref "C2") (pin "2") (pinfunction "2_2") (pintype "passive"))
      (node (ref "C20") (pin "2") (pinfunction "2_2") (pintype "passive"))
      (node (ref "C21") (pin "2") (pinfunction "2_2") (pintype "passive"))
      (node (ref "C22") (pin "2") (pinfunction "2_2") (pintype "passive"))
      (node (ref "C23") (pin "2") (pinfunction "2_2") (pintype "passive"))
      (node (ref "C24") (pin "2") (pinfunction "2_2") (pintype "passive"))
      (node (ref "C25") (pin "2") (pinfunction "2_2") (pintype "passive"))
      (node (ref "C26") (pin "2") (pinfunction "2_2") (pintype "passive"))
      (node (ref "C27") (pin "2") (pinfunction "2_2") (pintype "passive"))
      (node (ref "C28") (pin "2") (pinfunction "2_2") (pintype "passive"))
      (node (ref "C29") (pin "2") (pinfunction "2_2") (pintype "passive"))
      (node (ref "C3") (pin "2") (pinfunction "2_2") (pintype "passive"))
      (node (ref "C30") (pin "2") (pinfunction "2_2") (pintype "passive"))
      (node (ref "C31") (pin "2") (pinfunction "2_2") (pintype "passive"))
      (node (ref "C32") (pin "2") (pinfunction "2_2") (pintype "passive"))
      (node (ref "C33") (pin "2") (pinfunction "2_2") (pintype "passive"))
      (node (ref "C34") (pin "2") (pinfunction "2_2") (pintype "passive"))
      (node (ref "C35") (pin "2") (pinfunction "2_2") (pintype "passive"))
      (node (ref "C39") (pin "1") (pinfunction "1_1") (pintype "passive"))
      (node (ref "C4") (pin "2") (pinfunction "2_2") (pintype "passive"))
      (node (ref "C42") (pin "2") (pinfunction "2_2") (pintype "passive"))
      (node (ref "C43") (pin "2") (pinfunction "2_2") (pintype "passive"))
      (node (ref "C44") (pin "2") (pinfunction "2_2") (pintype "passive"))
      (node (ref "C45") (pin "2") (pinfunction "2_2") (pintype "passive"))
      (node (ref "C46") (pin "2") (pinfunction "2_2") (pintype "passive"))
      (node (ref "C47") (pin "2") (pinfunction "2_2") (pintype "passive"))
      (node (ref "C48") (pin "2") (pinfunction "2_2") (pintype "passive"))
      (node (ref "C49") (pin "2") (pinfunction "2_2") (pintype "passive"))
      (node (ref "C50") (pin "2") (pinfunction "2_2") (pintype "passive"))
      (node (ref "C51") (pin "2") (pinfunction "2_2") (pintype "passive"))
      (node (ref "C52") (pin "2") (pinfunction "2_2") (pintype "passive"))
      (node (ref "C53") (pin "2") (pinfunction "2_2") (pintype "passive"))
      (node (ref "C54") (pin "2") (pinfunction "2_2") (pintype "passive"))
      (node (ref "C55") (pin "2") (pinfunction "2_2") (pintype "passive"))
      (node (ref "C56") (pin "2") (pinfunction "2_2") (pintype "passive"))
      (node (ref "C57") (pin "2") (pinfunction "2_2") (pintype "passive"))
      (node (ref "C58") (pin "1") (pinfunction "1_1") (pintype "passive"))
      (node (ref "C8") (pin "2") (pinfunction "2_2") (pintype "passive"))
      (node (ref "IC11") (pin "2") (pinfunction "GND_2") (pintype "passive"))
      (node (ref "IC11") (pin "4") (pinfunction "GND_4") (pintype "passive"))
      (node (ref "IC15") (pin "2") (pinfunction "GND_2") (pintype "passive"))
      (node (ref "IC15") (pin "4") (pinfunction "GND_4") (pintype "passive"))
      (node (ref "IC16") (pin "2") (pinfunction "GND_2") (pintype "bidirectional"))
      (node (ref "IC17") (pin "2") (pinfunction "GND_2") (pintype "bidirectional"))
      (node (ref "IC18") (pin "3") (pinfunction "GND_3") (pintype "bidirectional"))
      (node (ref "IC18") (pin "8") (pinfunction "A_8") (pintype "bidirectional"))
      (node (ref "IC19") (pin "3") (pinfunction "GND_3") (pintype "bidirectional"))
      (node (ref "IC19") (pin "8") (pinfunction "A_8") (pintype "bidirectional"))
      (node (ref "IC2") (pin "2") (pinfunction "GND_2") (pintype "bidirectional"))
      (node (ref "IC20") (pin "3") (pinfunction "GND_3") (pintype "bidirectional"))
      (node (ref "IC20") (pin "8") (pinfunction "A_8") (pintype "bidirectional"))
      (node (ref "IC21") (pin "10") (pinfunction "S3B_10") (pintype "bidirectional"))
      (node (ref "IC21") (pin "13") (pinfunction "S4B_13") (pintype "bidirectional"))
      (node (ref "IC21") (pin "8") (pinfunction "GND_8") (pintype "bidirectional"))
      (node (ref "IC22") (pin "P$3") (pinfunction "RGND_P$3") (pintype "bidirectional"))
      (node (ref "IC22") (pin "P$6") (pinfunction "GND_P$6") (pintype "bidirectional"))
      (node (ref "IC23") (pin "3") (pinfunction "GND_3") (pintype "bidirectional"))
      (node (ref "IC24") (pin "P$3") (pinfunction "RGND_P$3") (pintype "bidirectional"))
      (node (ref "IC24") (pin "P$6") (pinfunction "GND_P$6") (pintype "bidirectional"))
      (node (ref "IC3") (pin "2") (pinfunction "GND_2") (pintype "bidirectional"))
      (node (ref "IC4") (pin "2") (pinfunction "GND_2") (pintype "bidirectional"))
      (node (ref "IC5") (pin "2") (pinfunction "GND_2") (pintype "bidirectional"))
      (node (ref "IC6") (pin "2") (pinfunction "GND_2") (pintype "bidirectional"))
      (node (ref "IC7") (pin "2") (pinfunction "GND_2") (pintype "bidirectional"))
      (node (ref "IC8") (pin "2") (pinfunction "GND_2") (pintype "bidirectional"))
      (node (ref "IC9") (pin "2") (pinfunction "GND_2") (pintype "passive"))
      (node (ref "IC9") (pin "4") (pinfunction "GND_4") (pintype "passive"))
      (node (ref "J1") (pin "B10") (pinfunction "B10_B10") (pintype "bidirectional"))
      (node (ref "J1") (pin "B11") (pinfunction "B11_B11") (pintype "bidirectional"))
      (node (ref "J1") (pin "B12") (pinfunction "B12_B12") (pintype "bidirectional"))
      (node (ref "J1") (pin "B13") (pinfunction "B13_B13") (pintype "bidirectional"))
      (node (ref "J1") (pin "B14") (pinfunction "B14_B14") (pintype "bidirectional"))
      (node (ref "J1") (pin "B15") (pinfunction "B15_B15") (pintype "bidirectional"))
      (node (ref "J1") (pin "B16") (pinfunction "B16_B16") (pintype "bidirectional"))
      (node (ref "J1") (pin "B17") (pinfunction "B17_B17") (pintype "bidirectional"))
      (node (ref "J1") (pin "B18") (pinfunction "B18_B18") (pintype "bidirectional"))
      (node (ref "J1") (pin "B19") (pinfunction "B19_B19") (pintype "bidirectional"))
      (node (ref "J1") (pin "B2") (pinfunction "B2_B2") (pintype "bidirectional"))
      (node (ref "J1") (pin "B20") (pinfunction "B20_B20") (pintype "bidirectional"))
      (node (ref "J1") (pin "B21") (pinfunction "B21_B21") (pintype "bidirectional"))
      (node (ref "J1") (pin "B22") (pinfunction "B22_B22") (pintype "bidirectional"))
      (node (ref "J1") (pin "B23") (pinfunction "B23_B23") (pintype "bidirectional"))
      (node (ref "J1") (pin "B24") (pinfunction "B24_B24") (pintype "bidirectional"))
      (node (ref "J1") (pin "B25") (pinfunction "B25_B25") (pintype "bidirectional"))
      (node (ref "J1") (pin "B26") (pinfunction "B26_B26") (pintype "bidirectional"))
      (node (ref "J1") (pin "B27") (pinfunction "B27_B27") (pintype "bidirectional"))
      (node (ref "J1") (pin "B28") (pinfunction "B28_B28") (pintype "bidirectional"))
      (node (ref "J1") (pin "B29") (pinfunction "B29_B29") (pintype "bidirectional"))
      (node (ref "J1") (pin "B30") (pinfunction "B30_B30") (pintype "bidirectional"))
      (node (ref "J1") (pin "B31") (pinfunction "B31_B31") (pintype "bidirectional"))
      (node (ref "J1") (pin "B32") (pinfunction "B32_B32") (pintype "bidirectional"))
      (node (ref "J1") (pin "B33") (pinfunction "B33_B33") (pintype "bidirectional"))
      (node (ref "J1") (pin "B34") (pinfunction "B34_B34") (pintype "bidirectional"))
      (node (ref "J1") (pin "B35") (pinfunction "B35_B35") (pintype "bidirectional"))
      (node (ref "J1") (pin "B36") (pinfunction "B36_B36") (pintype "bidirectional"))
      (node (ref "J1") (pin "B37") (pinfunction "B37_B37") (pintype "bidirectional"))
      (node (ref "J1") (pin "B38") (pinfunction "B38_B38") (pintype "bidirectional"))
      (node (ref "J1") (pin "B39") (pinfunction "B39_B39") (pintype "bidirectional"))
      (node (ref "J1") (pin "B40") (pinfunction "B40_B40") (pintype "bidirectional"))
      (node (ref "J1") (pin "B41") (pinfunction "B41_B41") (pintype "bidirectional"))
      (node (ref "J1") (pin "B42") (pinfunction "B42_B42") (pintype "bidirectional"))
      (node (ref "J1") (pin "B43") (pinfunction "B43_B43") (pintype "bidirectional"))
      (node (ref "J1") (pin "B44") (pinfunction "B44_B44") (pintype "bidirectional"))
      (node (ref "J1") (pin "B45") (pinfunction "B45_B45") (pintype "bidirectional"))
      (node (ref "J1") (pin "B47") (pinfunction "B47_B47") (pintype "bidirectional"))
      (node (ref "J1") (pin "B5") (pinfunction "B5_B5") (pintype "bidirectional"))
      (node (ref "J1") (pin "B6") (pinfunction "B6_B6") (pintype "bidirectional"))
      (node (ref "J1") (pin "B7") (pinfunction "B7_B7") (pintype "bidirectional"))
      (node (ref "J1") (pin "B8") (pinfunction "B8_B8") (pintype "bidirectional"))
      (node (ref "J1") (pin "B9") (pinfunction "B9_B9") (pintype "bidirectional"))
      (node (ref "JP14") (pin "1") (pinfunction "1_1") (pintype "passive"))
      (node (ref "JP17") (pin "3") (pinfunction "P$3_3") (pintype "bidirectional"))
      (node (ref "JP2") (pin "1") (pinfunction "1_1") (pintype "passive"))
      (node (ref "R15") (pin "1") (pinfunction "1_1") (pintype "passive"))
      (node (ref "R17") (pin "1") (pinfunction "1_1") (pintype "passive"))
      (node (ref "R19") (pin "1") (pinfunction "1_1") (pintype "passive"))
      (node (ref "R21") (pin "1") (pinfunction "1_1") (pintype "passive"))
      (node (ref "R23") (pin "1") (pinfunction "1_1") (pintype "passive"))
      (node (ref "R25") (pin "1") (pinfunction "1_1") (pintype "passive"))
      (node (ref "R27") (pin "1") (pinfunction "1_1") (pintype "passive"))
      (node (ref "R29") (pin "1") (pinfunction "1_1") (pintype "passive"))
      (node (ref "R31") (pin "1") (pinfunction "1_1") (pintype "passive"))
      (node (ref "R33") (pin "1") (pinfunction "1_1") (pintype "passive"))
      (node (ref "R35") (pin "1") (pinfunction "1_1") (pintype "passive"))
      (node (ref "R37") (pin "1") (pinfunction "1_1") (pintype "passive"))
      (node (ref "R39") (pin "1") (pinfunction "1_1") (pintype "passive"))
      (node (ref "R4") (pin "3") (pinfunction "3_3") (pintype "passive"))
      (node (ref "R41") (pin "1") (pinfunction "1_1") (pintype "passive"))
      (node (ref "R43") (pin "1") (pinfunction "1_1") (pintype "passive"))
      (node (ref "R5") (pin "3") (pinfunction "3_3") (pintype "passive"))
      (node (ref "R6") (pin "3") (pinfunction "3_3") (pintype "passive"))
      (node (ref "R8") (pin "1") (pinfunction "1_1") (pintype "passive"))
      (node (ref "R9") (pin "1") (pinfunction "1_1") (pintype "passive"))
      (node (ref "TP18") (pin "TP") (pinfunction "TP_TP") (pintype "input"))
      (node (ref "TP31") (pin "TP") (pinfunction "TP_TP") (pintype "input"))
      (node (ref "TP32") (pin "TP") (pinfunction "TP_TP") (pintype "input"))
      (node (ref "TP33") (pin "TP") (pinfunction "TP_TP") (pintype "input"))
      (node (ref "TP34") (pin "TP") (pinfunction "TP_TP") (pintype "input"))
      (node (ref "TP35") (pin "TP") (pinfunction "TP_TP") (pintype "input"))
      (node (ref "TP36") (pin "TP") (pinfunction "TP_TP") (pintype "input"))
      (node (ref "TP38") (pin "TP") (pinfunction "TP_TP") (pintype "input"))
    )
    (net (code "40") (name "/HOLD") (class "Default")
      (node (ref "IC1") (pin "37") (pinfunction "HOLD_37") (pintype "bidirectional"))
      (node (ref "R38") (pin "1") (pinfunction "1_1") (pintype "passive"))
      (node (ref "R39") (pin "2") (pinfunction "2_2") (pintype "passive"))
    )
    (net (code "41") (name "/HOLD_T") (class "Default")
      (node (ref "J1") (pin "A25") (pinfunction "A25_A25") (pintype "bidirectional"))
      (node (ref "R38") (pin "2") (pinfunction "2_2") (pintype "passive"))
    )
    (net (code "42") (name "/MUX_DAC_EN") (class "Default")
      (node (ref "IC21") (pin "15") (pinfunction "~{EN}_15") (pintype "bidirectional"))
      (node (ref "J1") (pin "A24") (pinfunction "A24_A24") (pintype "bidirectional"))
    )
    (net (code "43") (name "/MUX_DAC_SEL") (class "Default")
      (node (ref "IC21") (pin "1") (pinfunction "IN_1") (pintype "bidirectional"))
      (node (ref "J1") (pin "A23") (pinfunction "A23_A23") (pintype "bidirectional"))
    )
    (net (code "44") (name "/MUX_REF_1") (class "Default")
      (node (ref "IC2") (pin "6") (pinfunction "IN_6") (pintype "bidirectional"))
      (node (ref "J1") (pin "A13") (pinfunction "A13_A13") (pintype "bidirectional"))
    )
    (net (code "45") (name "/MUX_REF_2") (class "Default")
      (node (ref "IC3") (pin "6") (pinfunction "IN_6") (pintype "bidirectional"))
      (node (ref "J1") (pin "A11") (pinfunction "A11_A11") (pintype "bidirectional"))
    )
    (net (code "46") (name "/MUX_REF_3") (class "Default")
      (node (ref "IC4") (pin "6") (pinfunction "IN_6") (pintype "bidirectional"))
      (node (ref "J1") (pin "A9") (pinfunction "A9_A9") (pintype "bidirectional"))
    )
    (net (code "47") (name "/N$9") (class "Default")
      (node (ref "JP13") (pin "1") (pinfunction "1_1") (pintype "passive"))
      (node (ref "JP19") (pin "2") (pinfunction "2_2") (pintype "passive"))
    )
    (net (code "48") (name "/OP_MODE") (class "Default")
      (node (ref "IC1") (pin "11") (pinfunction "OP_MODE_11") (pintype "bidirectional"))
      (node (ref "R26") (pin "1") (pinfunction "1_1") (pintype "passive"))
      (node (ref "R27") (pin "2") (pinfunction "2_2") (pintype "passive"))
    )
    (net (code "49") (name "/OP_MODE_T") (class "Default")
      (node (ref "J1") (pin "A37") (pinfunction "A37_A37") (pintype "bidirectional"))
      (node (ref "R26") (pin "2") (pinfunction "2_2") (pintype "passive"))
    )
    (net (code "50") (name "/OUT_S") (class "Default")
      (node (ref "IC1") (pin "35") (pinfunction "OUT_S_35") (pintype "bidirectional"))
      (node (ref "R32") (pin "1") (pinfunction "1_1") (pintype "passive"))
      (node (ref "R33") (pin "2") (pinfunction "2_2") (pintype "passive"))
    )
    (net (code "51") (name "/OUT_S_T") (class "Default")
      (node (ref "J1") (pin "A22") (pinfunction "A22_A22") (pintype "bidirectional"))
      (node (ref "R32") (pin "2") (pinfunction "2_2") (pintype "passive"))
    )
    (net (code "52") (name "/POT_R1") (class "Default")
      (node (ref "JP4") (pin "3") (pinfunction "3_3") (pintype "passive"))
      (node (ref "R1") (pin "2") (pinfunction "2_2") (pintype "passive"))
      (node (ref "R1") (pin "3") (pinfunction "3_3") (pintype "passive"))
      (node (ref "TP27") (pin "TP") (pinfunction "TP_TP") (pintype "input"))
    )
    (net (code "53") (name "/POT_R2") (class "Default")
      (node (ref "JP4") (pin "1") (pinfunction "1_1") (pintype "passive"))
      (node (ref "R2") (pin "1") (pinfunction "1_1") (pintype "passive"))
      (node (ref "R2") (pin "2") (pinfunction "2_2") (pintype "passive"))
      (node (ref "TP28") (pin "TP") (pinfunction "TP_TP") (pintype "input"))
    )
    (net (code "54") (name "/POT_R4") (class "Default")
      (node (ref "IC2") (pin "3") (pinfunction "A1_3") (pintype "bidirectional"))
      (node (ref "R4") (pin "2") (pinfunction "2_2") (pintype "passive"))
      (node (ref "TP24") (pin "TP") (pinfunction "TP_TP") (pintype "input"))
    )
    (net (code "55") (name "/POT_R5") (class "Default")
      (node (ref "IC3") (pin "3") (pinfunction "A1_3") (pintype "bidirectional"))
      (node (ref "R5") (pin "2") (pinfunction "2_2") (pintype "passive"))
      (node (ref "TP25") (pin "TP") (pinfunction "TP_TP") (pintype "input"))
    )
    (net (code "56") (name "/POT_R6") (class "Default")
      (node (ref "IC4") (pin "3") (pinfunction "A1_3") (pintype "bidirectional"))
      (node (ref "R6") (pin "2") (pinfunction "2_2") (pintype "passive"))
      (node (ref "TP26") (pin "TP") (pinfunction "TP_TP") (pintype "input"))
    )
    (net (code "57") (name "/REFIN_DAC") (class "Default")
      (node (ref "C28") (pin "1") (pinfunction "1_1") (pintype "passive"))
      (node (ref "IC23") (pin "10") (pinfunction "REFIN_10") (pintype "bidirectional"))
      (node (ref "IC8") (pin "5") (pinfunction "VREF_5") (pintype "bidirectional"))
      (node (ref "TP15") (pin "TP") (pinfunction "TP_TP") (pintype "input"))
    )
    (net (code "58") (name "/REF_ADC") (class "Default")
      (node (ref "C17") (pin "1") (pinfunction "1_1") (pintype "passive"))
      (node (ref "C18") (pin "1") (pinfunction "1_1") (pintype "passive"))
      (node (ref "C23") (pin "1") (pinfunction "1_1") (pintype "passive"))
      (node (ref "C24") (pin "1") (pinfunction "1_1") (pintype "passive"))
      (node (ref "C31") (pin "1") (pinfunction "1_1") (pintype "passive"))
      (node (ref "IC17") (pin "5") (pinfunction "VREF_5") (pintype "bidirectional"))
      (node (ref "IC22") (pin "P$2") (pinfunction "REF_P$2") (pintype "bidirectional"))
      (node (ref "IC24") (pin "P$2") (pinfunction "REF_P$2") (pintype "bidirectional"))
      (node (ref "TP17") (pin "TP") (pinfunction "TP_TP") (pintype "input"))
    )
    (net (code "59") (name "/RES_BIAS_EXT") (class "Default")
      (node (ref "IC1") (pin "6") (pinfunction "RES_BIAS_EXT_6") (pintype "bidirectional"))
      (node (ref "JP4") (pin "2") (pinfunction "2_2") (pintype "passive"))
    )
    (net (code "60") (name "/RST") (class "Default")
      (node (ref "IC1") (pin "38") (pinfunction "RST_38") (pintype "bidirectional"))
      (node (ref "R36") (pin "1") (pinfunction "1_1") (pintype "passive"))
      (node (ref "R37") (pin "2") (pinfunction "2_2") (pintype "passive"))
    )
    (net (code "61") (name "/RST_CSA") (class "Default")
      (node (ref "IC1") (pin "12") (pinfunction "RST_CSA_12") (pintype "bidirectional"))
      (node (ref "R28") (pin "1") (pinfunction "1_1") (pintype "passive"))
      (node (ref "R29") (pin "2") (pinfunction "2_2") (pintype "passive"))
    )
    (net (code "62") (name "/RST_CSA_T") (class "Default")
      (node (ref "J1") (pin "A35") (pinfunction "A35_A35") (pintype "bidirectional"))
      (node (ref "R28") (pin "2") (pinfunction "2_2") (pintype "passive"))
    )
    (net (code "63") (name "/RST_T") (class "Default")
      (node (ref "J1") (pin "A26") (pinfunction "A26_A26") (pintype "bidirectional"))
      (node (ref "R36") (pin "2") (pinfunction "2_2") (pintype "passive"))
    )
    (net (code "64") (name "/SDI_DAC") (class "Default")
      (node (ref "IC23") (pin "7") (pinfunction "DIN_7") (pintype "bidirectional"))
      (node (ref "J1") (pin "A20") (pinfunction "A20_A20") (pintype "bidirectional"))
    )
    (net (code "65") (name "/SDI_REF") (class "Default")
      (node (ref "IC18") (pin "5") (pinfunction "SDI_5") (pintype "bidirectional"))
      (node (ref "IC19") (pin "5") (pinfunction "SDI_5") (pintype "bidirectional"))
      (node (ref "IC20") (pin "5") (pinfunction "SDI_5") (pintype "bidirectional"))
      (node (ref "J1") (pin "A6") (pinfunction "A6_A6") (pintype "bidirectional"))
    )
    (net (code "66") (name "/SDO_ADC1") (class "Default")
      (node (ref "IC22") (pin "P$8") (pinfunction "DOUT_P$8") (pintype "bidirectional"))
      (node (ref "J1") (pin "A43") (pinfunction "A43_A43") (pintype "bidirectional"))
      (node (ref "R3") (pin "1") (pinfunction "1_1") (pintype "passive"))
    )
    (net (code "67") (name "/SDO_ADC2") (class "Default")
      (node (ref "IC24") (pin "P$8") (pinfunction "DOUT_P$8") (pintype "bidirectional"))
      (node (ref "J1") (pin "A16") (pinfunction "A16_A16") (pintype "bidirectional"))
      (node (ref "R7") (pin "1") (pinfunction "1_1") (pintype "passive"))
    )
    (net (code "68") (name "/SGN") (class "Default")
      (node (ref "IC1") (pin "39") (pinfunction "SGN_39") (pintype "bidirectional"))
      (node (ref "R34") (pin "1") (pinfunction "1_1") (pintype "passive"))
      (node (ref "R35") (pin "2") (pinfunction "2_2") (pintype "passive"))
    )
    (net (code "69") (name "/SGN_T") (class "Default")
      (node (ref "J1") (pin "A27") (pinfunction "A27_A27") (pintype "bidirectional"))
      (node (ref "R34") (pin "2") (pinfunction "2_2") (pintype "passive"))
    )
    (net (code "70") (name "/V0NDAC") (class "Default")
      (node (ref "IC21") (pin "5") (pinfunction "S2A_5") (pintype "bidirectional"))
      (node (ref "IC23") (pin "2") (pinfunction "VOUTB_2") (pintype "bidirectional"))
    )
    (net (code "71") (name "/V0PDAC") (class "Default")
      (node (ref "IC21") (pin "2") (pinfunction "S1A_2") (pintype "bidirectional"))
      (node (ref "IC23") (pin "1") (pinfunction "VOUTA_1") (pintype "bidirectional"))
    )
    (net (code "72") (name "/V1NDAC") (class "Default")
      (node (ref "C53") (pin "1") (pinfunction "1_1") (pintype "passive"))
      (node (ref "IC21") (pin "14") (pinfunction "S4A_14") (pintype "bidirectional"))
      (node (ref "IC23") (pin "5") (pinfunction "VOUTD_5") (pintype "bidirectional"))
    )
    (net (code "73") (name "/V1PDAC") (class "Default")
      (node (ref "C52") (pin "1") (pinfunction "1_1") (pintype "passive"))
      (node (ref "IC21") (pin "11") (pinfunction "S3A_11") (pintype "bidirectional"))
      (node (ref "IC23") (pin "4") (pinfunction "VOUTC_4") (pintype "bidirectional"))
    )
    (net (code "74") (name "/VDD") (class "Default")
      (node (ref "C1") (pin "1") (pinfunction "1_1") (pintype "passive"))
      (node (ref "C2") (pin "1") (pinfunction "1_1") (pintype "passive"))
      (node (ref "C3") (pin "1") (pinfunction "1_1") (pintype "passive"))
      (node (ref "C39") (pin "2") (pinfunction "2_2") (pintype "passive"))
      (node (ref "C44") (pin "1") (pinfunction "1_1") (pintype "passive"))
      (node (ref "C58") (pin "2") (pinfunction "2_2") (pintype "passive"))
      (node (ref "IC11") (pin "3") (pinfunction "VO_3") (pintype "passive"))
      (node (ref "IC18") (pin "2") (pinfunction "VDD_2") (pintype "bidirectional"))
      (node (ref "IC19") (pin "2") (pinfunction "VDD_2") (pintype "bidirectional"))
      (node (ref "IC2") (pin "5") (pinfunction "VCC_5") (pintype "bidirectional"))
      (node (ref "IC20") (pin "2") (pinfunction "VDD_2") (pintype "bidirectional"))
      (node (ref "IC21") (pin "16") (pinfunction "VDD_16") (pintype "bidirectional"))
      (node (ref "IC23") (pin "8") (pinfunction "VDD_8") (pintype "bidirectional"))
      (node (ref "IC3") (pin "5") (pinfunction "VCC_5") (pintype "bidirectional"))
      (node (ref "IC4") (pin "5") (pinfunction "VCC_5") (pintype "bidirectional"))
      (node (ref "IC5") (pin "3") (pinfunction "EN_3") (pintype "bidirectional"))
      (node (ref "IC5") (pin "4") (pinfunction "VIN_4") (pintype "bidirectional"))
      (node (ref "IC6") (pin "3") (pinfunction "EN_3") (pintype "bidirectional"))
      (node (ref "IC6") (pin "4") (pinfunction "VIN_4") (pintype "bidirectional"))
      (node (ref "IC7") (pin "3") (pinfunction "EN_3") (pintype "bidirectional"))
      (node (ref "IC7") (pin "4") (pinfunction "VIN_4") (pintype "bidirectional"))
      (node (ref "TP5") (pin "TP") (pinfunction "TP_TP") (pintype "input"))
    )
    (net (code "75") (name "/VDD2") (class "Default")
      (node (ref "C46") (pin "1") (pinfunction "1_1") (pintype "passive"))
      (node (ref "C5") (pin "1") (pinfunction "1_1") (pintype "passive"))
      (node (ref "C7") (pin "1") (pinfunction "1_1") (pintype "passive"))
      (node (ref "IC10") (pin "3") (pinfunction "EN_3") (pintype "bidirectional"))
      (node (ref "IC10") (pin "4") (pinfunction "VIN_4") (pintype "bidirectional"))
      (node (ref "IC13") (pin "3") (pinfunction "EN_3") (pintype "bidirectional"))
      (node (ref "IC13") (pin "4") (pinfunction "VIN_4") (pintype "bidirectional"))
      (node (ref "IC9") (pin "3") (pinfunction "VO_3") (pintype "passive"))
      (node (ref "TP6") (pin "TP") (pinfunction "TP_TP") (pintype "input"))
    )
    (net (code "76") (name "/VDD3") (class "Default")
      (node (ref "C15") (pin "1") (pinfunction "1_1") (pintype "passive"))
      (node (ref "C16") (pin "1") (pinfunction "1_1") (pintype "passive"))
      (node (ref "C19") (pin "1") (pinfunction "1_1") (pintype "passive"))
      (node (ref "C20") (pin "1") (pinfunction "1_1") (pintype "passive"))
      (node (ref "C25") (pin "1") (pinfunction "1_1") (pintype "passive"))
      (node (ref "C30") (pin "1") (pinfunction "1_1") (pintype "passive"))
      (node (ref "C4") (pin "1") (pinfunction "1_1") (pintype "passive"))
      (node (ref "C51") (pin "1") (pinfunction "1_1") (pintype "passive"))
      (node (ref "IC12") (pin "8") (pinfunction "V+_8") (pintype "bidirectional"))
      (node (ref "IC14") (pin "8") (pinfunction "V+_8") (pintype "bidirectional"))
      (node (ref "IC15") (pin "3") (pinfunction "VO_3") (pintype "passive"))
      (node (ref "IC16") (pin "3") (pinfunction "EN_3") (pintype "bidirectional"))
      (node (ref "IC16") (pin "4") (pinfunction "VIN_4") (pintype "bidirectional"))
      (node (ref "IC17") (pin "3") (pinfunction "EN_3") (pintype "bidirectional"))
      (node (ref "IC17") (pin "4") (pinfunction "VIN_4") (pintype "bidirectional"))
      (node (ref "IC22") (pin "P$4") (pinfunction "VDD_P$4") (pintype "bidirectional"))
      (node (ref "IC24") (pin "P$4") (pinfunction "VDD_P$4") (pintype "bidirectional"))
      (node (ref "IC8") (pin "3") (pinfunction "EN_3") (pintype "bidirectional"))
      (node (ref "IC8") (pin "4") (pinfunction "VIN_4") (pintype "bidirectional"))
      (node (ref "TP45") (pin "TP") (pinfunction "TP_TP") (pintype "input"))
    )
    (net (code "77") (name "/VDD_REF_1") (class "Default")
      (node (ref "C26") (pin "1") (pinfunction "1_1") (pintype "passive"))
      (node (ref "IC18") (pin "7") (pinfunction "B_7") (pintype "bidirectional"))
      (node (ref "IC5") (pin "5") (pinfunction "VREF_5") (pintype "bidirectional"))
      (node (ref "R4") (pin "1") (pinfunction "1_1") (pintype "passive"))
      (node (ref "TP41") (pin "TP") (pinfunction "TP_TP") (pintype "input"))
    )
    (net (code "78") (name "/VDD_REF_2") (class "Default")
      (node (ref "C27") (pin "1") (pinfunction "1_1") (pintype "passive"))
      (node (ref "IC19") (pin "7") (pinfunction "B_7") (pintype "bidirectional"))
      (node (ref "IC6") (pin "5") (pinfunction "VREF_5") (pintype "bidirectional"))
      (node (ref "R5") (pin "1") (pinfunction "1_1") (pintype "passive"))
      (node (ref "TP42") (pin "TP") (pinfunction "TP_TP") (pintype "input"))
    )
    (net (code "79") (name "/VDD_REF_3") (class "Default")
      (node (ref "C35") (pin "1") (pinfunction "1_1") (pintype "passive"))
      (node (ref "IC20") (pin "7") (pinfunction "B_7") (pintype "bidirectional"))
      (node (ref "IC7") (pin "5") (pinfunction "VREF_5") (pintype "bidirectional"))
      (node (ref "R6") (pin "1") (pinfunction "1_1") (pintype "passive"))
      (node (ref "TP43") (pin "TP") (pinfunction "TP_TP") (pintype "input"))
    )
    (net (code "80") (name "/VDD_SUPPLY_1") (class "Default")
      (node (ref "C43") (pin "1") (pinfunction "1_1") (pintype "passive"))
      (node (ref "IC11") (pin "1") (pinfunction "VI_1") (pintype "input"))
      (node (ref "JP5") (pin "1") (pinfunction "1_1") (pintype "passive"))
      (node (ref "TP1") (pin "TP") (pinfunction "TP_TP") (pintype "input"))
    )
    (net (code "81") (name "/VDD_SUPPLY_2") (class "Default")
      (node (ref "C45") (pin "1") (pinfunction "1_1") (pintype "passive"))
      (node (ref "IC9") (pin "1") (pinfunction "VI_1") (pintype "input"))
      (node (ref "JP8") (pin "1") (pinfunction "1_1") (pintype "passive"))
      (node (ref "TP3") (pin "TP") (pinfunction "TP_TP") (pintype "input"))
    )
    (net (code "82") (name "/VDD_SUPPLY_3") (class "Default")
      (node (ref "C50") (pin "1") (pinfunction "1_1") (pintype "passive"))
      (node (ref "IC15") (pin "1") (pinfunction "VI_1") (pintype "input"))
      (node (ref "JP20") (pin "1") (pinfunction "1_1") (pintype "passive"))
      (node (ref "TP44") (pin "TP") (pinfunction "TP_TP") (pintype "input"))
    )
    (net (code "83") (name "/VDD_SUPPLY_IN_1") (class "Default")
      (node (ref "JP17") (pin "1") (pinfunction "P$1_1") (pintype "bidirectional"))
      (node (ref "JP20") (pin "2") (pinfunction "2_2") (pintype "passive"))
      (node (ref "JP5") (pin "2") (pinfunction "2_2") (pintype "passive"))
      (node (ref "TP2") (pin "TP") (pinfunction "TP_TP") (pintype "input"))
    )
    (net (code "84") (name "/VDD_SUPPLY_IN_2") (class "Default")
      (node (ref "JP17") (pin "2") (pinfunction "P$2_2") (pintype "bidirectional"))
      (node (ref "JP8") (pin "2") (pinfunction "2_2") (pintype "passive"))
      (node (ref "TP4") (pin "TP") (pinfunction "TP_TP") (pintype "input"))
    )
    (net (code "85") (name "/VI+_FIL") (class "Default")
      (node (ref "IC1") (pin "22") (pinfunction "VI+_FIL_22") (pintype "input"))
      (node (ref "JP11") (pin "2") (pinfunction "2_2") (pintype "passive"))
    )
    (net (code "86") (name "/VI+_FIL_DAC") (class "Default")
      (node (ref "C54") (pin "1") (pinfunction "1_1") (pintype "passive"))
      (node (ref "IC21") (pin "4") (pinfunction "D1_4") (pintype "bidirectional"))
      (node (ref "JP11") (pin "1") (pinfunction "1_1") (pintype "passive"))
    )
    (net (code "87") (name "/VI-_FIL") (class "Default")
      (node (ref "IC1") (pin "23") (pinfunction "VI-_FIL_23") (pintype "input"))
      (node (ref "JP12") (pin "2") (pinfunction "2_2") (pintype "passive"))
    )
    (net (code "88") (name "/VI-_FIL_DAC") (class "Default")
      (node (ref "C55") (pin "1") (pinfunction "1_1") (pintype "passive"))
      (node (ref "IC21") (pin "7") (pinfunction "D2_7") (pintype "bidirectional"))
      (node (ref "JP12") (pin "1") (pinfunction "1_1") (pintype "passive"))
    )
    (net (code "89") (name "/VICM") (class "Default")
      (node (ref "IC1") (pin "40") (pinfunction "VICM_40") (pintype "input"))
      (node (ref "IC21") (pin "3") (pinfunction "S1B_3") (pintype "bidirectional"))
      (node (ref "IC21") (pin "6") (pinfunction "S2B_6") (pintype "bidirectional"))
      (node (ref "JP15") (pin "2") (pinfunction "2_2") (pintype "passive"))
      (node (ref "TP12") (pin "TP") (pinfunction "TP_TP") (pintype "input"))
    )
    (net (code "90") (name "/VICM_BUFF") (class "Default")
      (node (ref "C32") (pin "1") (pinfunction "1_1") (pintype "passive"))
      (node (ref "IC12") (pin "1") (pinfunction "OUTA_1") (pintype "bidirectional"))
      (node (ref "IC12") (pin "2") (pinfunction "-INA_2") (pintype "bidirectional"))
      (node (ref "JP15") (pin "1") (pinfunction "1_1") (pintype "passive"))
    )
    (net (code "91") (name "/VICM_MUX") (class "Default")
      (node (ref "C47") (pin "1") (pinfunction "1_1") (pintype "passive"))
      (node (ref "IC12") (pin "3") (pinfunction "+INA_3") (pintype "bidirectional"))
      (node (ref "IC3") (pin "4") (pinfunction "B_4") (pintype "bidirectional"))
      (node (ref "JP15") (pin "3") (pinfunction "3_3") (pintype "passive"))
      (node (ref "TP11") (pin "TP") (pinfunction "TP_TP") (pintype "input"))
    )
    (net (code "92") (name "/VIN_CSA") (class "Default")
      (node (ref "IC1") (pin "15") (pinfunction "VIN_CSA_15") (pintype "input"))
      (node (ref "JP1") (pin "3") (pinfunction "3_3") (pintype "passive"))
      (node (ref "JP10") (pin "2") (pinfunction "2_2") (pintype "passive"))
      (node (ref "TP20") (pin "TP") (pinfunction "TP_TP") (pintype "input"))
    )
    (net (code "93") (name "/VIN_CSA_1") (class "Default")
      (node (ref "C36") (pin "1") (pinfunction "1_1") (pintype "passive"))
      (node (ref "C56") (pin "1") (pinfunction "1_1") (pintype "passive"))
      (node (ref "IC21") (pin "9") (pinfunction "D3_9") (pintype "bidirectional"))
      (node (ref "JP9") (pin "1") (pinfunction "1_1") (pintype "passive"))
    )
    (net (code "94") (name "/VL_ADC") (class "Default")
      (node (ref "C14") (pin "1") (pinfunction "1_1") (pintype "passive"))
      (node (ref "C21") (pin "1") (pinfunction "1_1") (pintype "passive"))
      (node (ref "C22") (pin "1") (pinfunction "1_1") (pintype "passive"))
      (node (ref "C29") (pin "1") (pinfunction "1_1") (pintype "passive"))
      (node (ref "C8") (pin "1") (pinfunction "1_1") (pintype "passive"))
      (node (ref "IC16") (pin "5") (pinfunction "VREF_5") (pintype "bidirectional"))
      (node (ref "IC22") (pin "P$7") (pinfunction "VL_P$7") (pintype "bidirectional"))
      (node (ref "IC24") (pin "P$7") (pinfunction "VL_P$7") (pintype "bidirectional"))
      (node (ref "R3") (pin "2") (pinfunction "2_2") (pintype "passive"))
      (node (ref "R7") (pin "2") (pinfunction "2_2") (pintype "passive"))
      (node (ref "TP16") (pin "TP") (pinfunction "TP_TP") (pintype "input"))
    )
    (net (code "95") (name "/VO+_BP_FIL") (class "Default")
      (node (ref "IC1") (pin "24") (pinfunction "VO+_BP_FIL_24") (pintype "output"))
      (node (ref "JP3") (pin "3") (pinfunction "3_3") (pintype "passive"))
    )
    (net (code "96") (name "/VO+_CH") (class "Default")
      (node (ref "IC1") (pin "50") (pinfunction "VO+_CH_50") (pintype "input"))
      (node (ref "JP13") (pin "3") (pinfunction "3_3") (pintype "passive"))
    )
    (net (code "97") (name "/VO+_FIL") (class "Default")
      (node (ref "IC1") (pin "30") (pinfunction "VO+_FIL_30") (pintype "output"))
      (node (ref "JP3") (pin "1") (pinfunction "1_1") (pintype "passive"))
    )
    (net (code "98") (name "/VO-_BP_FIL") (class "Default")
      (node (ref "IC1") (pin "25") (pinfunction "VO-_BP_FIL_25") (pintype "output"))
      (node (ref "JP18") (pin "3") (pinfunction "3_3") (pintype "passive"))
    )
    (net (code "99") (name "/VO-_CH") (class "Default")
      (node (ref "IC1") (pin "52") (pinfunction "VO-_CH_52") (pintype "input"))
      (node (ref "JP14") (pin "3") (pinfunction "3_3") (pintype "passive"))
    )
    (net (code "100") (name "/VO-_FIL") (class "Default")
      (node (ref "IC1") (pin "31") (pinfunction "VO-_FIL_31") (pintype "output"))
      (node (ref "JP18") (pin "1") (pinfunction "1_1") (pintype "passive"))
    )
    (net (code "101") (name "/VOCM") (class "Default")
      (node (ref "IC1") (pin "34") (pinfunction "VOCM_AUX_34") (pintype "input"))
      (node (ref "IC1") (pin "36") (pinfunction "VOCM_36") (pintype "input"))
      (node (ref "JP16") (pin "2") (pinfunction "2_2") (pintype "passive"))
      (node (ref "TP14") (pin "TP") (pinfunction "TP_TP") (pintype "input"))
    )
    (net (code "102") (name "/VOCM_1") (class "Default")
      (node (ref "C49") (pin "1") (pinfunction "1_1") (pintype "passive"))
      (node (ref "IC14") (pin "3") (pinfunction "+INA_3") (pintype "bidirectional"))
      (node (ref "IC2") (pin "4") (pinfunction "B_4") (pintype "bidirectional"))
      (node (ref "JP7") (pin "3") (pinfunction "3_3") (pintype "passive"))
      (node (ref "TP30") (pin "TP") (pinfunction "TP_TP") (pintype "input"))
    )
    (net (code "103") (name "/VOCM_BUFF") (class "Default")
      (node (ref "C33") (pin "1") (pinfunction "1_1") (pintype "passive"))
      (node (ref "IC12") (pin "6") (pinfunction "-INB_6") (pintype "bidirectional"))
      (node (ref "IC12") (pin "7") (pinfunction "OUTB_7") (pintype "bidirectional"))
      (node (ref "JP16") (pin "1") (pinfunction "1_1") (pintype "passive"))
    )
    (net (code "104") (name "/VOCM_MUX") (class "Default")
      (node (ref "C48") (pin "1") (pinfunction "1_1") (pintype "passive"))
      (node (ref "IC12") (pin "5") (pinfunction "+INB_5") (pintype "bidirectional"))
      (node (ref "IC4") (pin "4") (pinfunction "B_4") (pintype "bidirectional"))
      (node (ref "JP16") (pin "3") (pinfunction "3_3") (pintype "passive"))
      (node (ref "TP13") (pin "TP") (pinfunction "TP_TP") (pintype "input"))
    )
    (net (code "105") (name "/VOUT_CSA") (class "Default")
      (node (ref "IC1") (pin "54") (pinfunction "VOUT_CSA_54") (pintype "output"))
      (node (ref "JP19") (pin "3") (pinfunction "3_3") (pintype "passive"))
      (node (ref "TP9") (pin "TP") (pinfunction "TP_TP") (pintype "input"))
    )
    (net (code "106") (name "/VSS") (class "Default")
      (node (ref "IC12") (pin "4") (pinfunction "V-_4") (pintype "bidirectional"))
      (node (ref "IC14") (pin "4") (pinfunction "V-_4") (pintype "bidirectional"))
      (node (ref "JP17") (pin "4") (pinfunction "P$4_4") (pintype "bidirectional"))
      (node (ref "TP39") (pin "TP") (pinfunction "TP_TP") (pintype "input"))
    )
    (net (code "107") (name "/V_REF_PRECHAR") (class "Default")
      (node (ref "IC1") (pin "7") (pinfunction "V_REF_PRECHAR_7") (pintype "input"))
      (node (ref "JP7") (pin "2") (pinfunction "2_2") (pintype "passive"))
      (node (ref "TP37") (pin "TP") (pinfunction "TP_TP") (pintype "input"))
    )
    (net (code "108") (name "/V_REF_PRECHAR_BUFF") (class "Default")
      (node (ref "C34") (pin "1") (pinfunction "1_1") (pintype "passive"))
      (node (ref "IC14") (pin "1") (pinfunction "OUTA_1") (pintype "bidirectional"))
      (node (ref "IC14") (pin "2") (pinfunction "-INA_2") (pintype "bidirectional"))
      (node (ref "JP7") (pin "1") (pinfunction "1_1") (pintype "passive"))
    )
    (net (code "109") (name "/~{CS_ADC1}") (class "Default")
      (node (ref "IC22") (pin "P$9") (pinfunction "CNVST_P$9") (pintype "bidirectional"))
      (node (ref "J1") (pin "A44") (pinfunction "A44_A44") (pintype "bidirectional"))
    )
    (net (code "110") (name "/~{CS_ADC2}") (class "Default")
      (node (ref "IC24") (pin "P$9") (pinfunction "CNVST_P$9") (pintype "bidirectional"))
      (node (ref "J1") (pin "A17") (pinfunction "A17_A17") (pintype "bidirectional"))
    )
    (net (code "111") (name "/~{CS_DAC}") (class "Default")
      (node (ref "IC23") (pin "9") (pinfunction "~{SYNC}_9") (pintype "bidirectional"))
      (node (ref "J1") (pin "A19") (pinfunction "A19_A19") (pintype "bidirectional"))
    )
    (net (code "112") (name "Net-(C36-Pad2)") (class "Default")
      (node (ref "C36") (pin "2") (pinfunction "2_2") (pintype "passive"))
      (node (ref "C37") (pin "1") (pinfunction "1_1") (pintype "passive"))
      (node (ref "JP9") (pin "2") (pinfunction "2_2") (pintype "passive"))
    )
    (net (code "113") (name "Net-(C37-Pad2)") (class "Default")
      (node (ref "C37") (pin "2") (pinfunction "2_2") (pintype "passive"))
      (node (ref "JP10") (pin "1") (pinfunction "1_1") (pintype "passive"))
    )
    (net (code "114") (name "Net-(C38-Pad1)") (class "Default")
      (node (ref "C38") (pin "1") (pinfunction "1_1") (pintype "passive"))
      (node (ref "JP1") (pin "2") (pinfunction "2_2") (pintype "passive"))
    )
    (net (code "115") (name "Net-(C42-Pad1)") (class "Default")
      (node (ref "C42") (pin "1") (pinfunction "1_1") (pintype "passive"))
      (node (ref "J1") (pin "B50") (pinfunction "B50_B50") (pintype "bidirectional"))
      (node (ref "R8") (pin "2") (pinfunction "2_2") (pintype "passive"))
    )
    (net (code "116") (name "Net-(IC18-W)") (class "Default")
      (node (ref "IC18") (pin "1") (pinfunction "W_1") (pintype "bidirectional"))
      (node (ref "IC2") (pin "1") (pinfunction "A0_1") (pintype "bidirectional"))
    )
    (net (code "117") (name "Net-(IC19-W)") (class "Default")
      (node (ref "IC19") (pin "1") (pinfunction "W_1") (pintype "bidirectional"))
      (node (ref "IC3") (pin "1") (pinfunction "A0_1") (pintype "bidirectional"))
    )
    (net (code "118") (name "Net-(IC20-W)") (class "Default")
      (node (ref "IC20") (pin "1") (pinfunction "W_1") (pintype "bidirectional"))
      (node (ref "IC4") (pin "1") (pinfunction "A0_1") (pintype "bidirectional"))
    )
    (net (code "119") (name "Net-(J1-PadA46)") (class "Default")
      (node (ref "J1") (pin "A46") (pinfunction "A46_A46") (pintype "bidirectional"))
      (node (ref "J1") (pin "A48") (pinfunction "A48_A48") (pintype "bidirectional"))
    )
    (net (code "120") (name "Net-(J1-PadB1)") (class "Default")
      (node (ref "J1") (pin "B1") (pinfunction "B1_B1") (pintype "bidirectional"))
      (node (ref "R9") (pin "2") (pinfunction "2_2") (pintype "passive"))
    )
    (net (code "121") (name "unconnected-(IC5-N{slash}C-Pad1)") (class "Default")
      (node (ref "IC5") (pin "1") (pinfunction "N/C_1") (pintype "bidirectional"))
    )
    (net (code "122") (name "unconnected-(IC6-N{slash}C-Pad1)") (class "Default")
      (node (ref "IC6") (pin "1") (pinfunction "N/C_1") (pintype "bidirectional"))
    )
    (net (code "123") (name "unconnected-(IC7-N{slash}C-Pad1)") (class "Default")
      (node (ref "IC7") (pin "1") (pinfunction "N/C_1") (pintype "bidirectional"))
    )
    (net (code "124") (name "unconnected-(IC8-N{slash}C-Pad1)") (class "Default")
      (node (ref "IC8") (pin "1") (pinfunction "N/C_1") (pintype "bidirectional"))
    )
    (net (code "125") (name "unconnected-(IC10-N{slash}C-Pad1)") (class "Default")
      (node (ref "IC10") (pin "1") (pinfunction "N/C_1") (pintype "bidirectional"))
    )
    (net (code "126") (name "unconnected-(IC13-N{slash}C-Pad1)") (class "Default")
      (node (ref "IC13") (pin "1") (pinfunction "N/C_1") (pintype "bidirectional"))
    )
    (net (code "127") (name "unconnected-(IC14-+INB-Pad5)") (class "Default")
      (node (ref "IC14") (pin "5") (pinfunction "+INB_5") (pintype "bidirectional"))
    )
    (net (code "128") (name "unconnected-(IC14--INB-Pad6)") (class "Default")
      (node (ref "IC14") (pin "6") (pinfunction "-INB_6") (pintype "bidirectional"))
    )
    (net (code "129") (name "unconnected-(IC14-OUTB-Pad7)") (class "Default")
      (node (ref "IC14") (pin "7") (pinfunction "OUTB_7") (pintype "bidirectional"))
    )
    (net (code "130") (name "unconnected-(IC16-N{slash}C-Pad1)") (class "Default")
      (node (ref "IC16") (pin "1") (pinfunction "N/C_1") (pintype "bidirectional"))
    )
    (net (code "131") (name "unconnected-(IC17-N{slash}C-Pad1)") (class "Default")
      (node (ref "IC17") (pin "1") (pinfunction "N/C_1") (pintype "bidirectional"))
    )
    (net (code "132") (name "unconnected-(J1-PadA1)") (class "Default")
      (node (ref "J1") (pin "A1") (pinfunction "A1_A1") (pintype "bidirectional"))
    )
    (net (code "133") (name "unconnected-(J1-PadA2)") (class "Default")
      (node (ref "J1") (pin "A2") (pinfunction "A2_A2") (pintype "bidirectional"))
    )
    (net (code "134") (name "unconnected-(J1-PadA3)") (class "Default")
      (node (ref "J1") (pin "A3") (pinfunction "A3_A3") (pintype "bidirectional"))
    )
    (net (code "135") (name "unconnected-(J1-PadA4)") (class "Default")
      (node (ref "J1") (pin "A4") (pinfunction "A4_A4") (pintype "bidirectional"))
    )
    (net (code "136") (name "unconnected-(J1-PadA5)") (class "Default")
      (node (ref "J1") (pin "A5") (pinfunction "A5_A5") (pintype "bidirectional"))
    )
    (net (code "137") (name "unconnected-(J1-PadA14)") (class "Default")
      (node (ref "J1") (pin "A14") (pinfunction "A14_A14") (pintype "bidirectional"))
    )
    (net (code "138") (name "unconnected-(J1-PadA15)") (class "Default")
      (node (ref "J1") (pin "A15") (pinfunction "A15_A15") (pintype "bidirectional"))
    )
    (net (code "139") (name "unconnected-(J1-PadA29)") (class "Default")
      (node (ref "J1") (pin "A29") (pinfunction "A29_A29") (pintype "bidirectional"))
    )
    (net (code "140") (name "unconnected-(J1-PadA31)") (class "Default")
      (node (ref "J1") (pin "A31") (pinfunction "A31_A31") (pintype "bidirectional"))
    )
    (net (code "141") (name "unconnected-(J1-PadA39)") (class "Default")
      (node (ref "J1") (pin "A39") (pinfunction "A39_A39") (pintype "bidirectional"))
    )
    (net (code "142") (name "unconnected-(J1-PadA41)") (class "Default")
      (node (ref "J1") (pin "A41") (pinfunction "A41_A41") (pintype "bidirectional"))
    )
    (net (code "143") (name "unconnected-(J1-PadA47)") (class "Default")
      (node (ref "J1") (pin "A47") (pinfunction "A47_A47") (pintype "bidirectional"))
    )
    (net (code "144") (name "unconnected-(J1-PadA49)") (class "Default")
      (node (ref "J1") (pin "A49") (pinfunction "A49_A49") (pintype "bidirectional"))
    )
    (net (code "145") (name "unconnected-(J1-PadA50)") (class "Default")
      (node (ref "J1") (pin "A50") (pinfunction "A50_A50") (pintype "bidirectional"))
    )
    (net (code "146") (name "unconnected-(J1-PadB3)") (class "Default")
      (node (ref "J1") (pin "B3") (pinfunction "B3_B3") (pintype "bidirectional"))
    )
    (net (code "147") (name "unconnected-(J1-PadB4)") (class "Default")
      (node (ref "J1") (pin "B4") (pinfunction "B4_B4") (pintype "bidirectional"))
    )
    (net (code "148") (name "unconnected-(J1-PadB46)") (class "Default")
      (node (ref "J1") (pin "B46") (pinfunction "B46_B46") (pintype "bidirectional"))
    )
    (net (code "149") (name "unconnected-(J1-PadB48)") (class "Default")
      (node (ref "J1") (pin "B48") (pinfunction "B48_B48") (pintype "bidirectional"))
    )
    (net (code "150") (name "unconnected-(J1-PadB49)") (class "Default")
      (node (ref "J1") (pin "B49") (pinfunction "B49_B49") (pintype "bidirectional"))
    )
  )
)
